# canSlaveV06.net
KiCad netlist of a schematic drawn in EAGLE
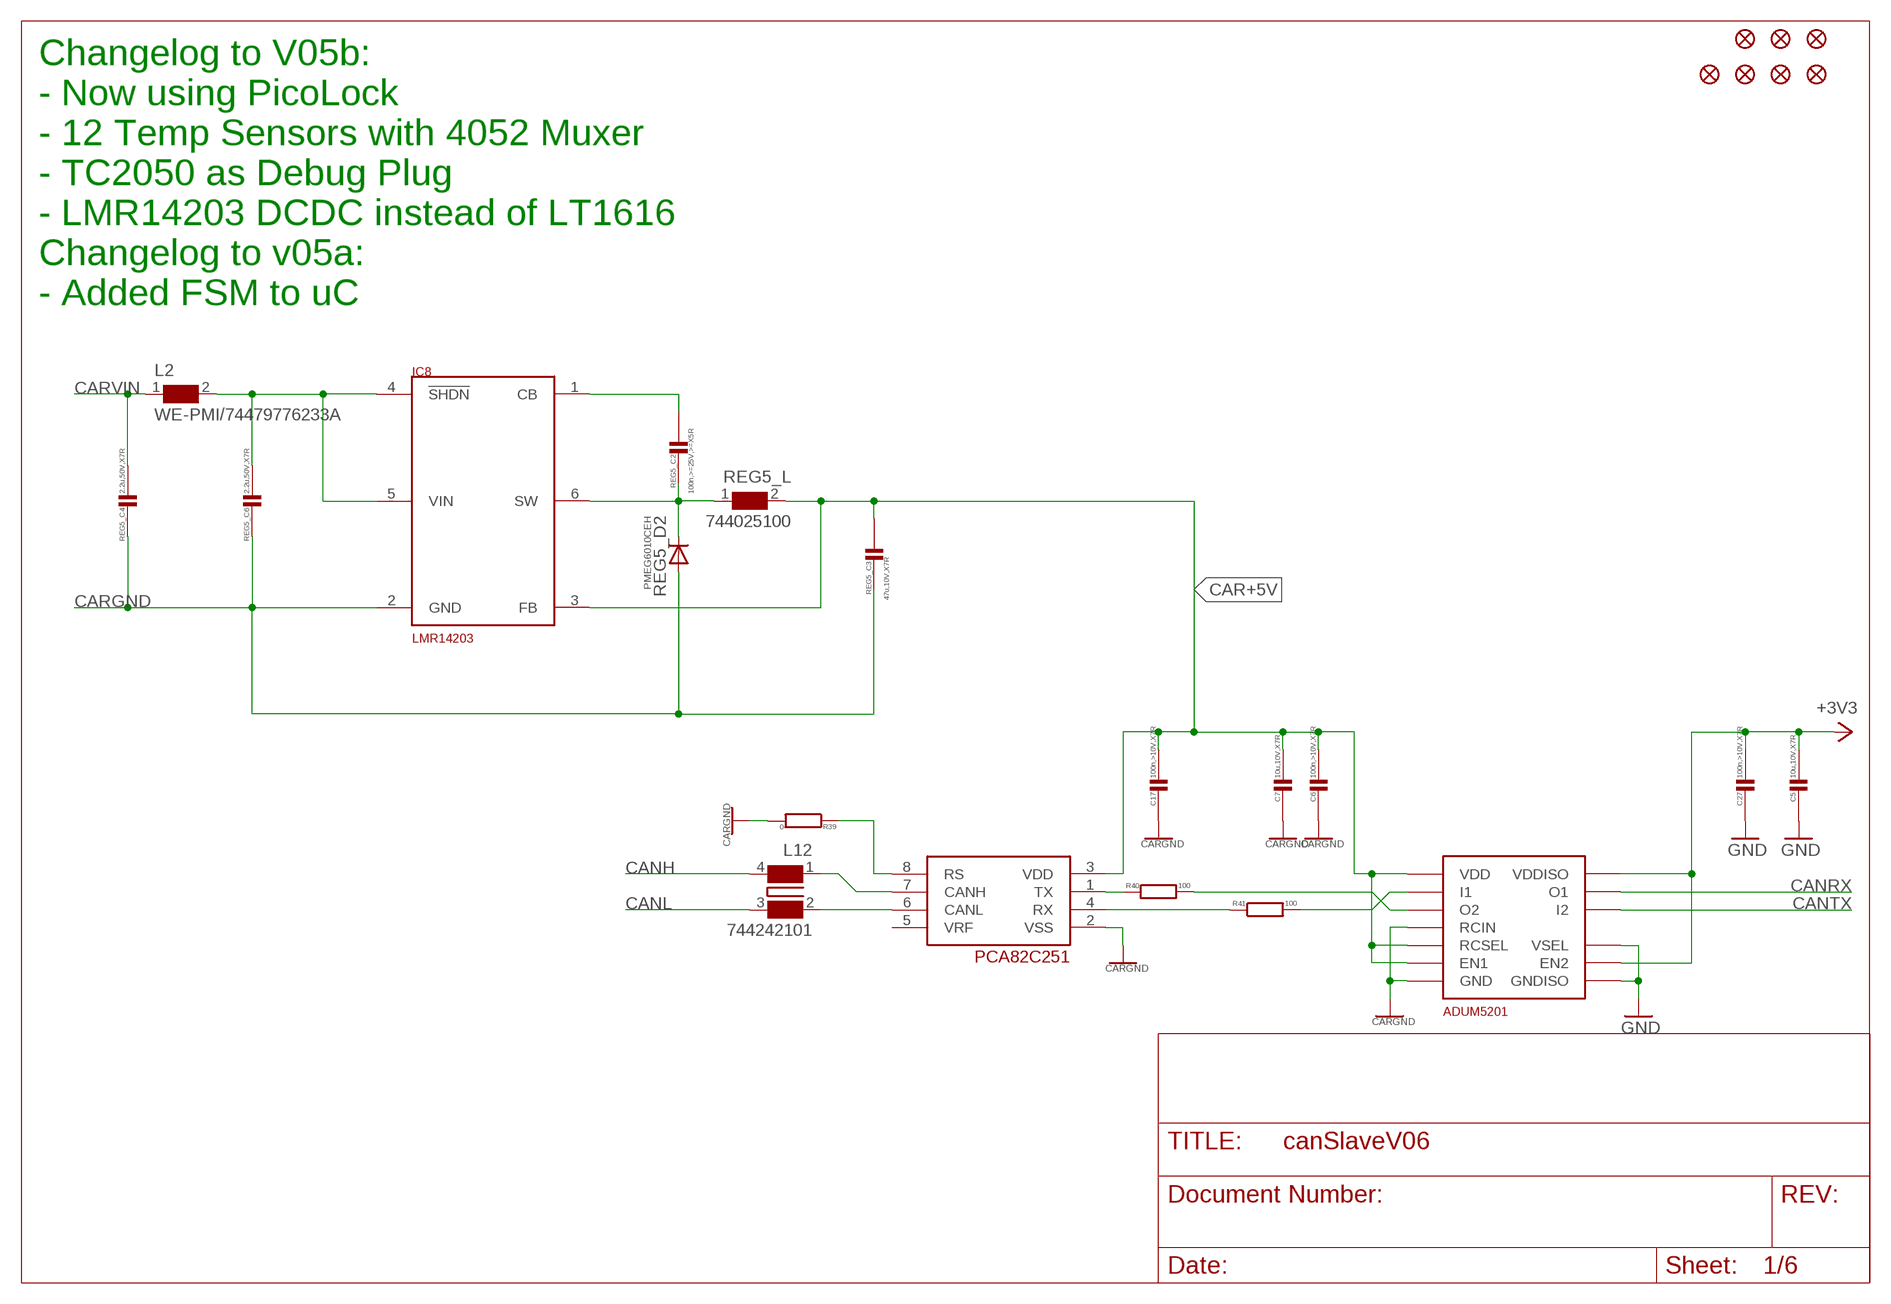
[diagram p0: schematic, sheet 1]
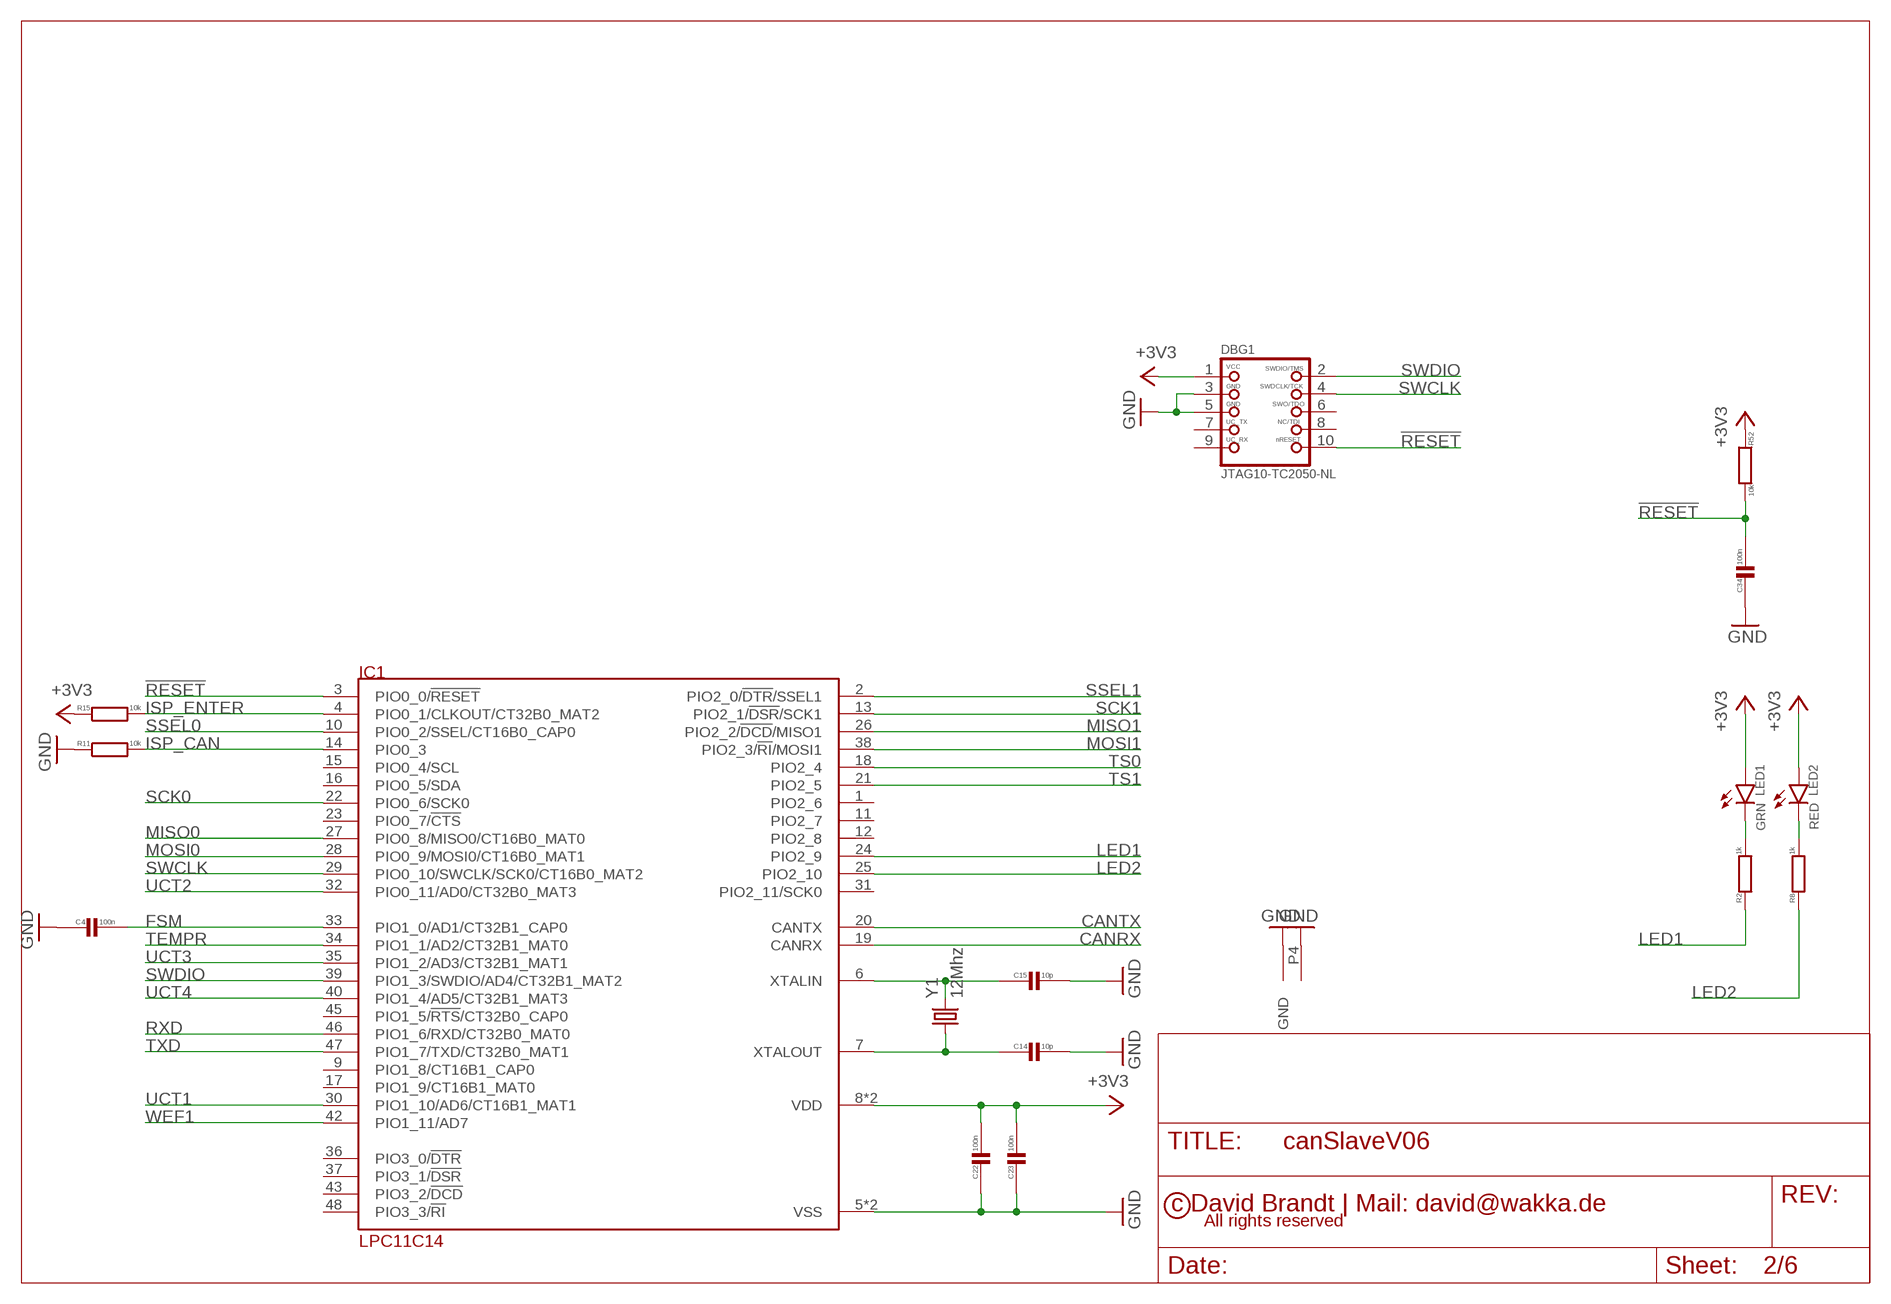
[diagram p1: schematic, sheet 2]
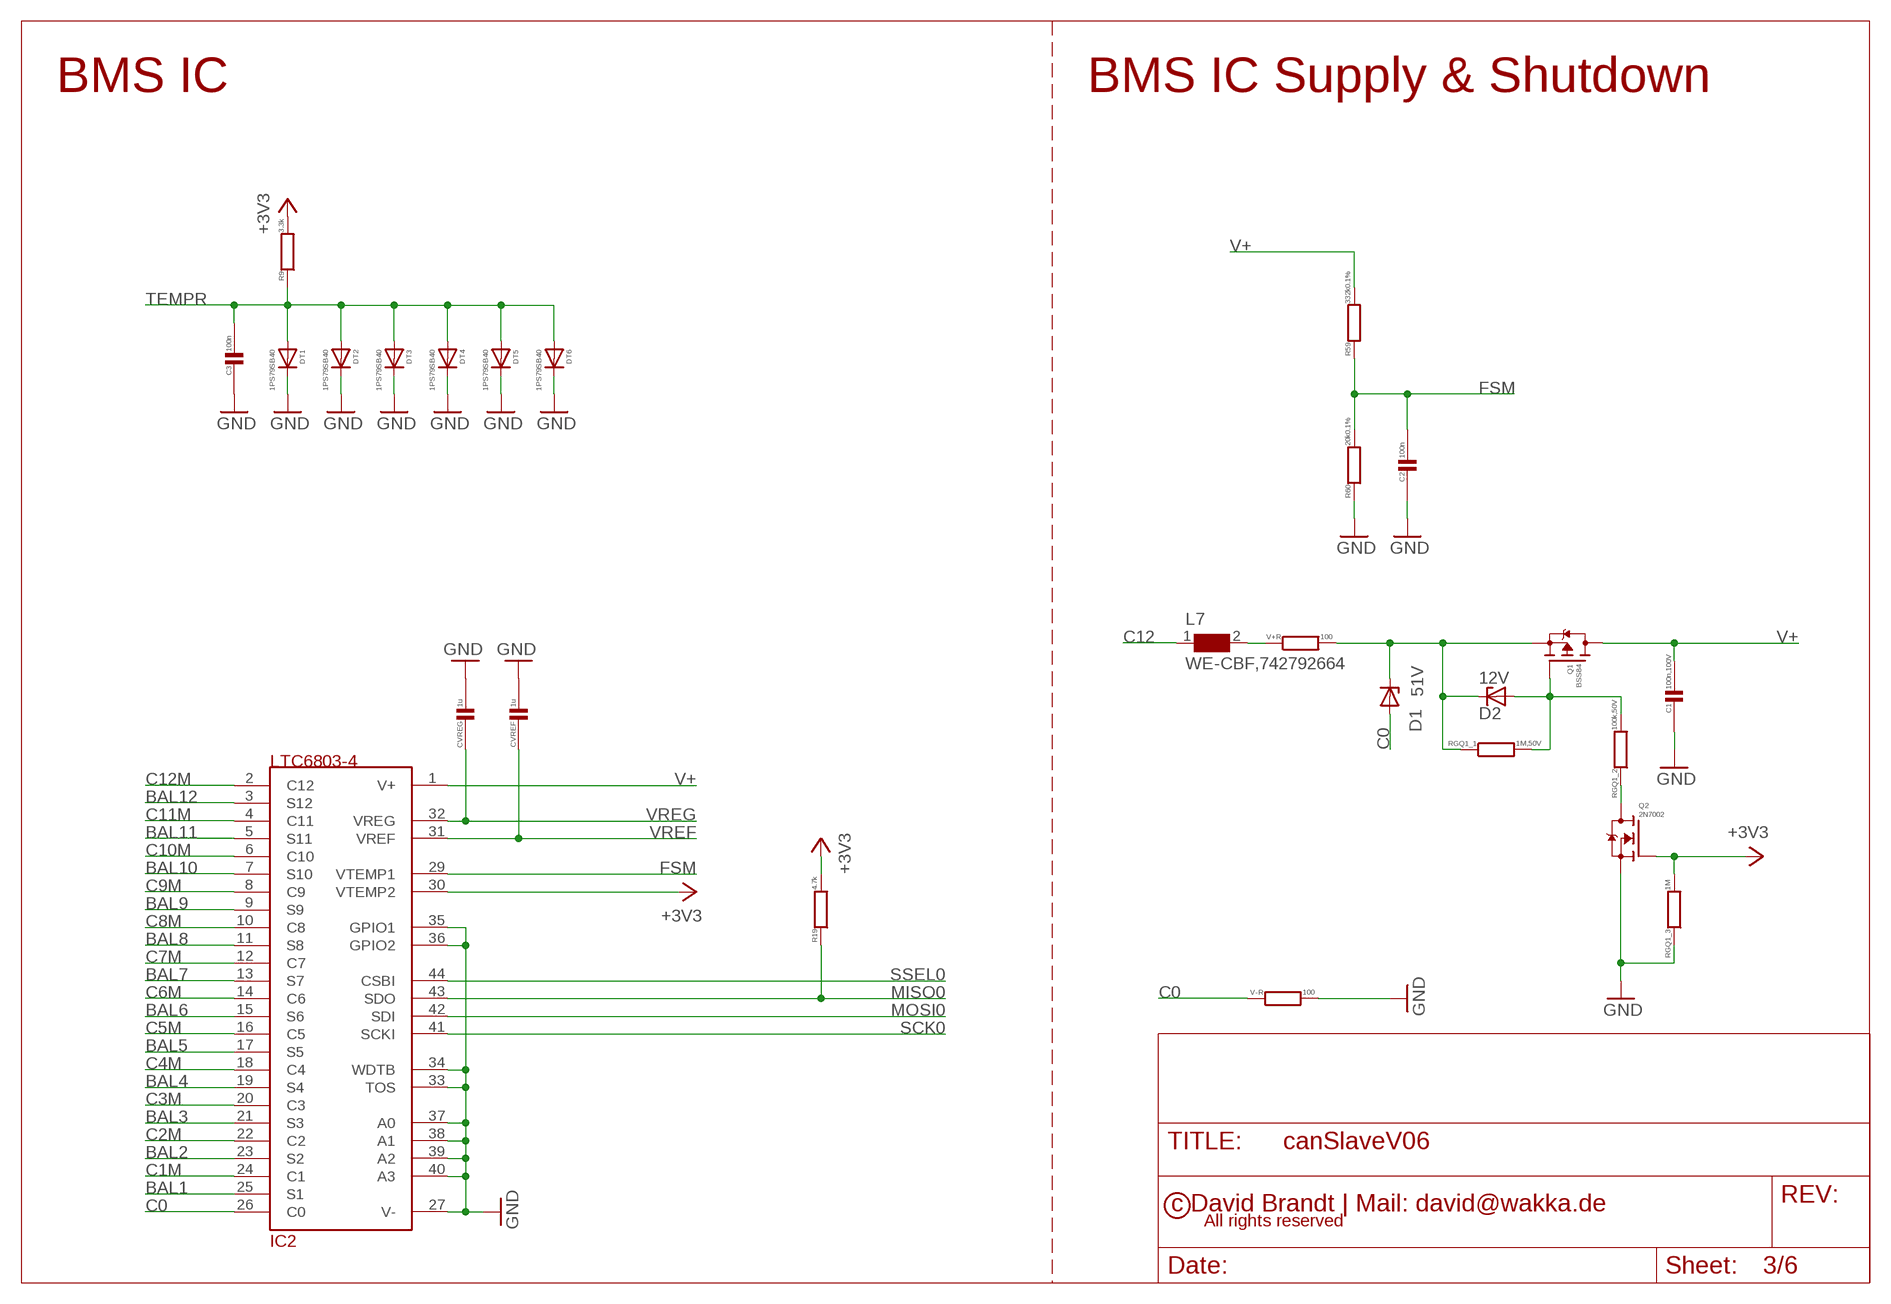
[diagram p2: schematic, sheet 3]
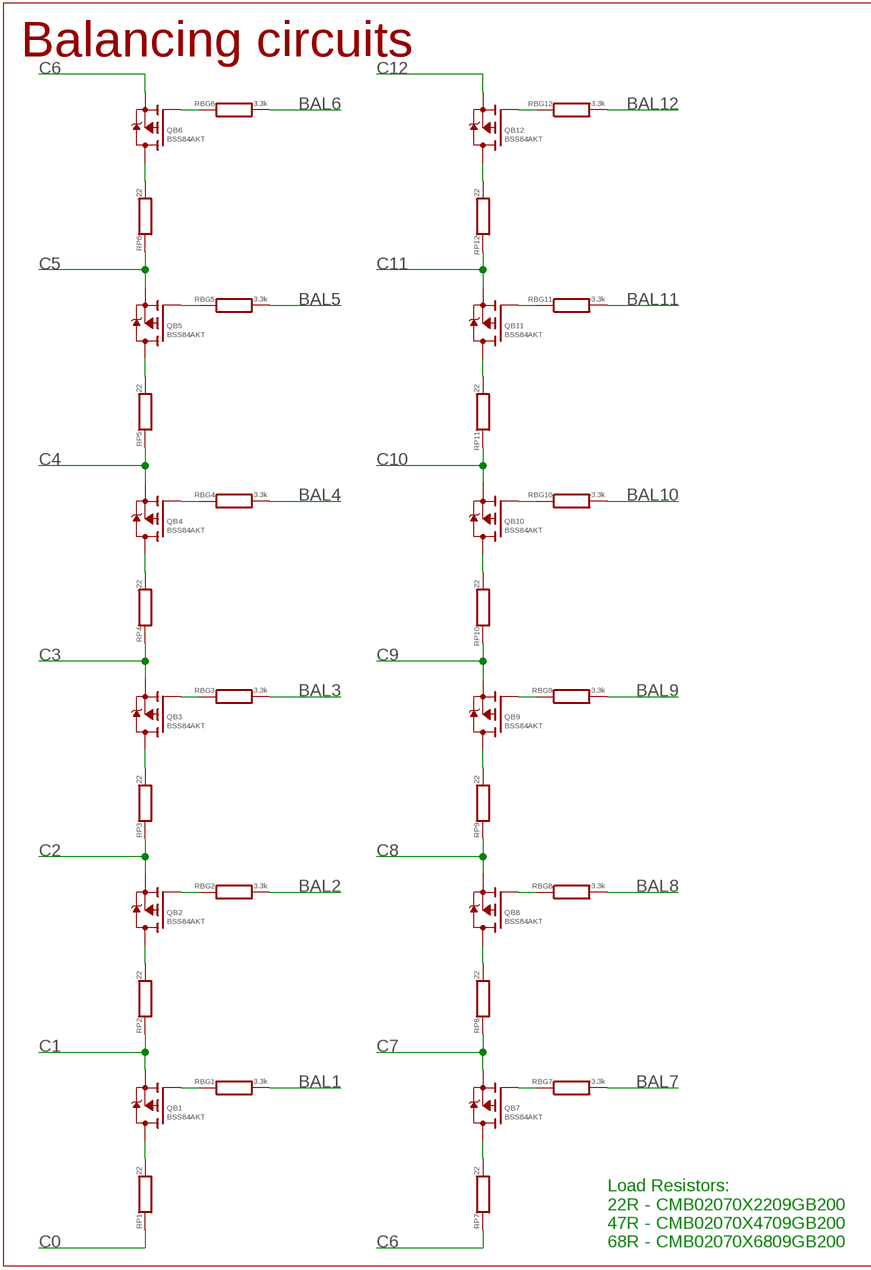
[diagram p3: schematic, sheet 4, part 1 of 2]
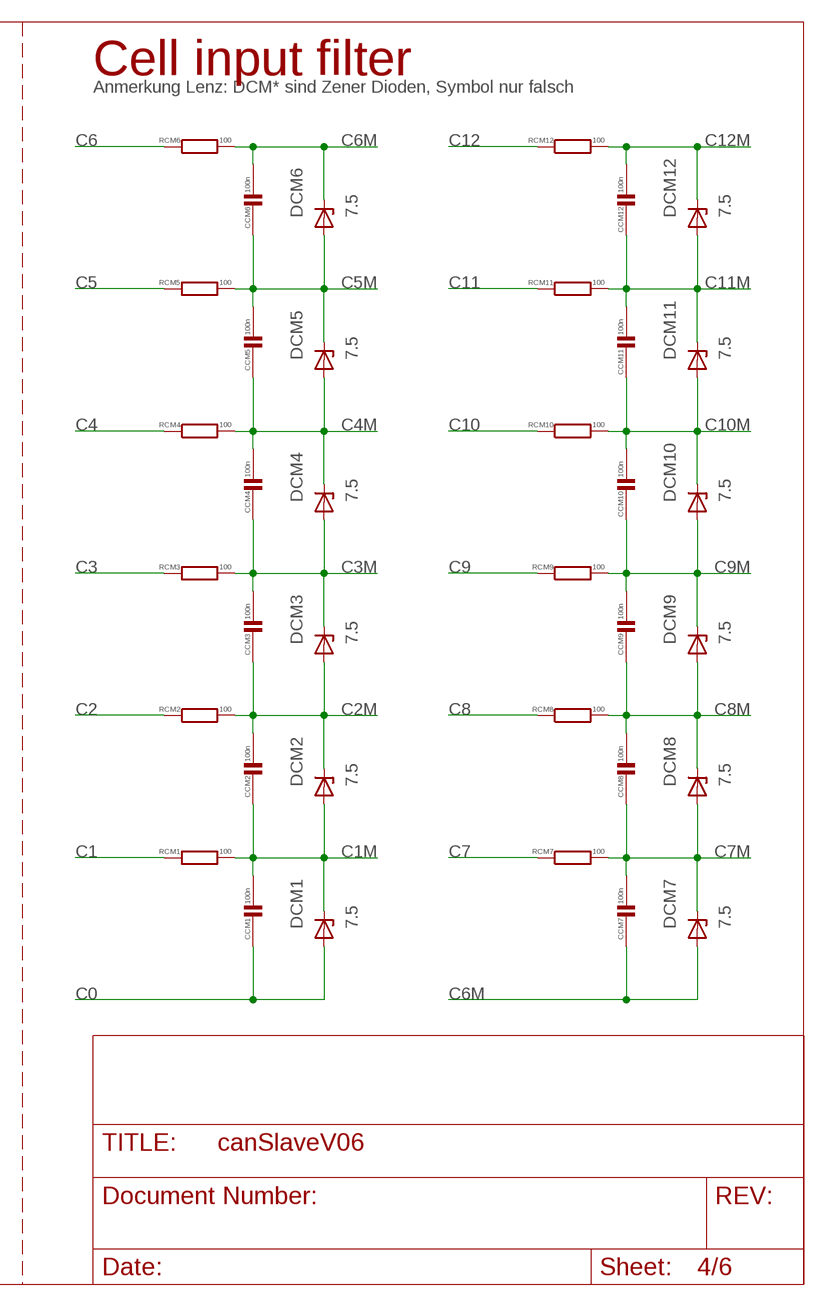
[diagram p4: schematic, sheet 4, part 2 of 2]
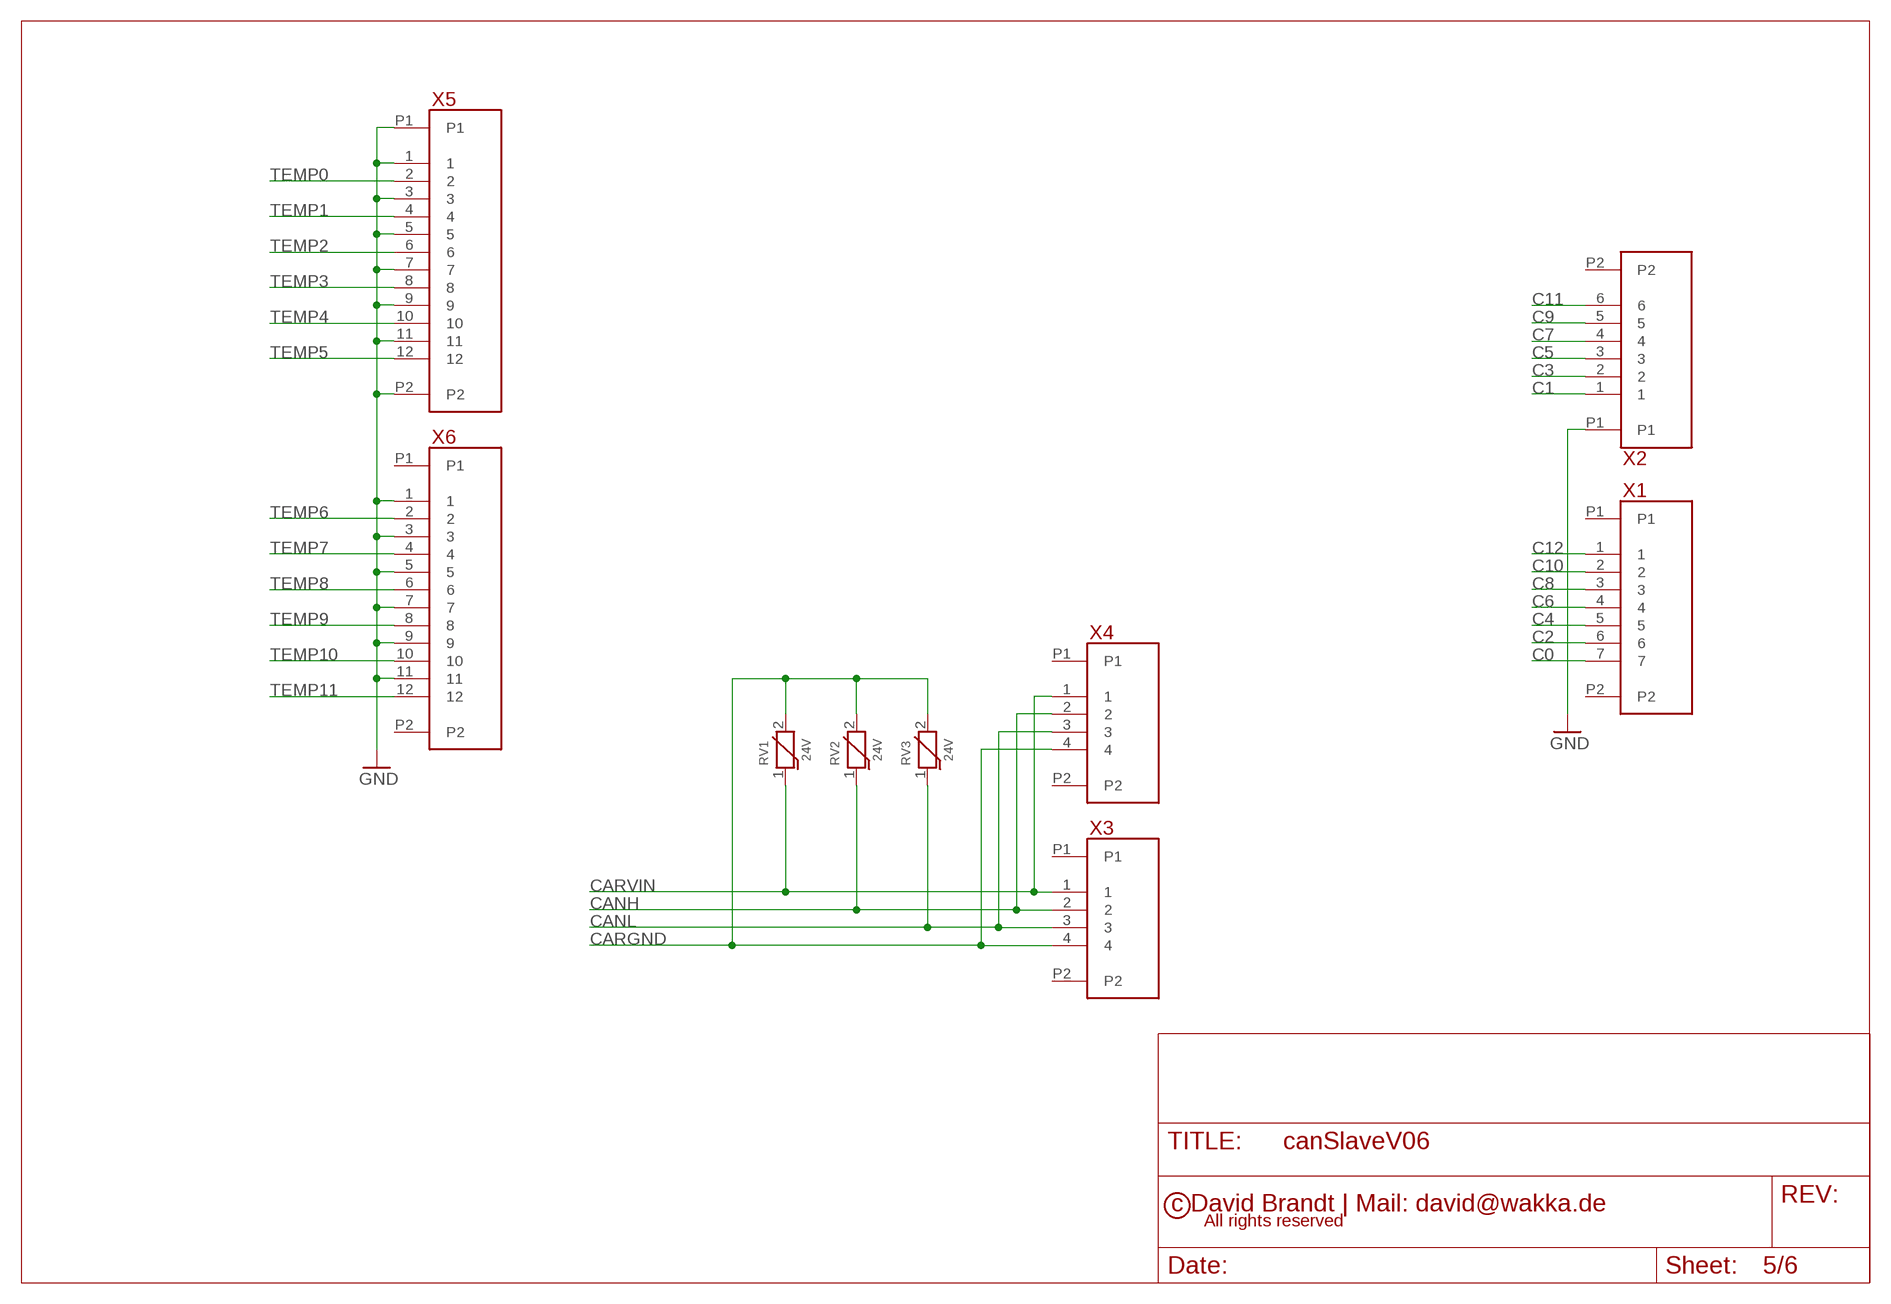
[diagram p5: schematic, sheet 5]
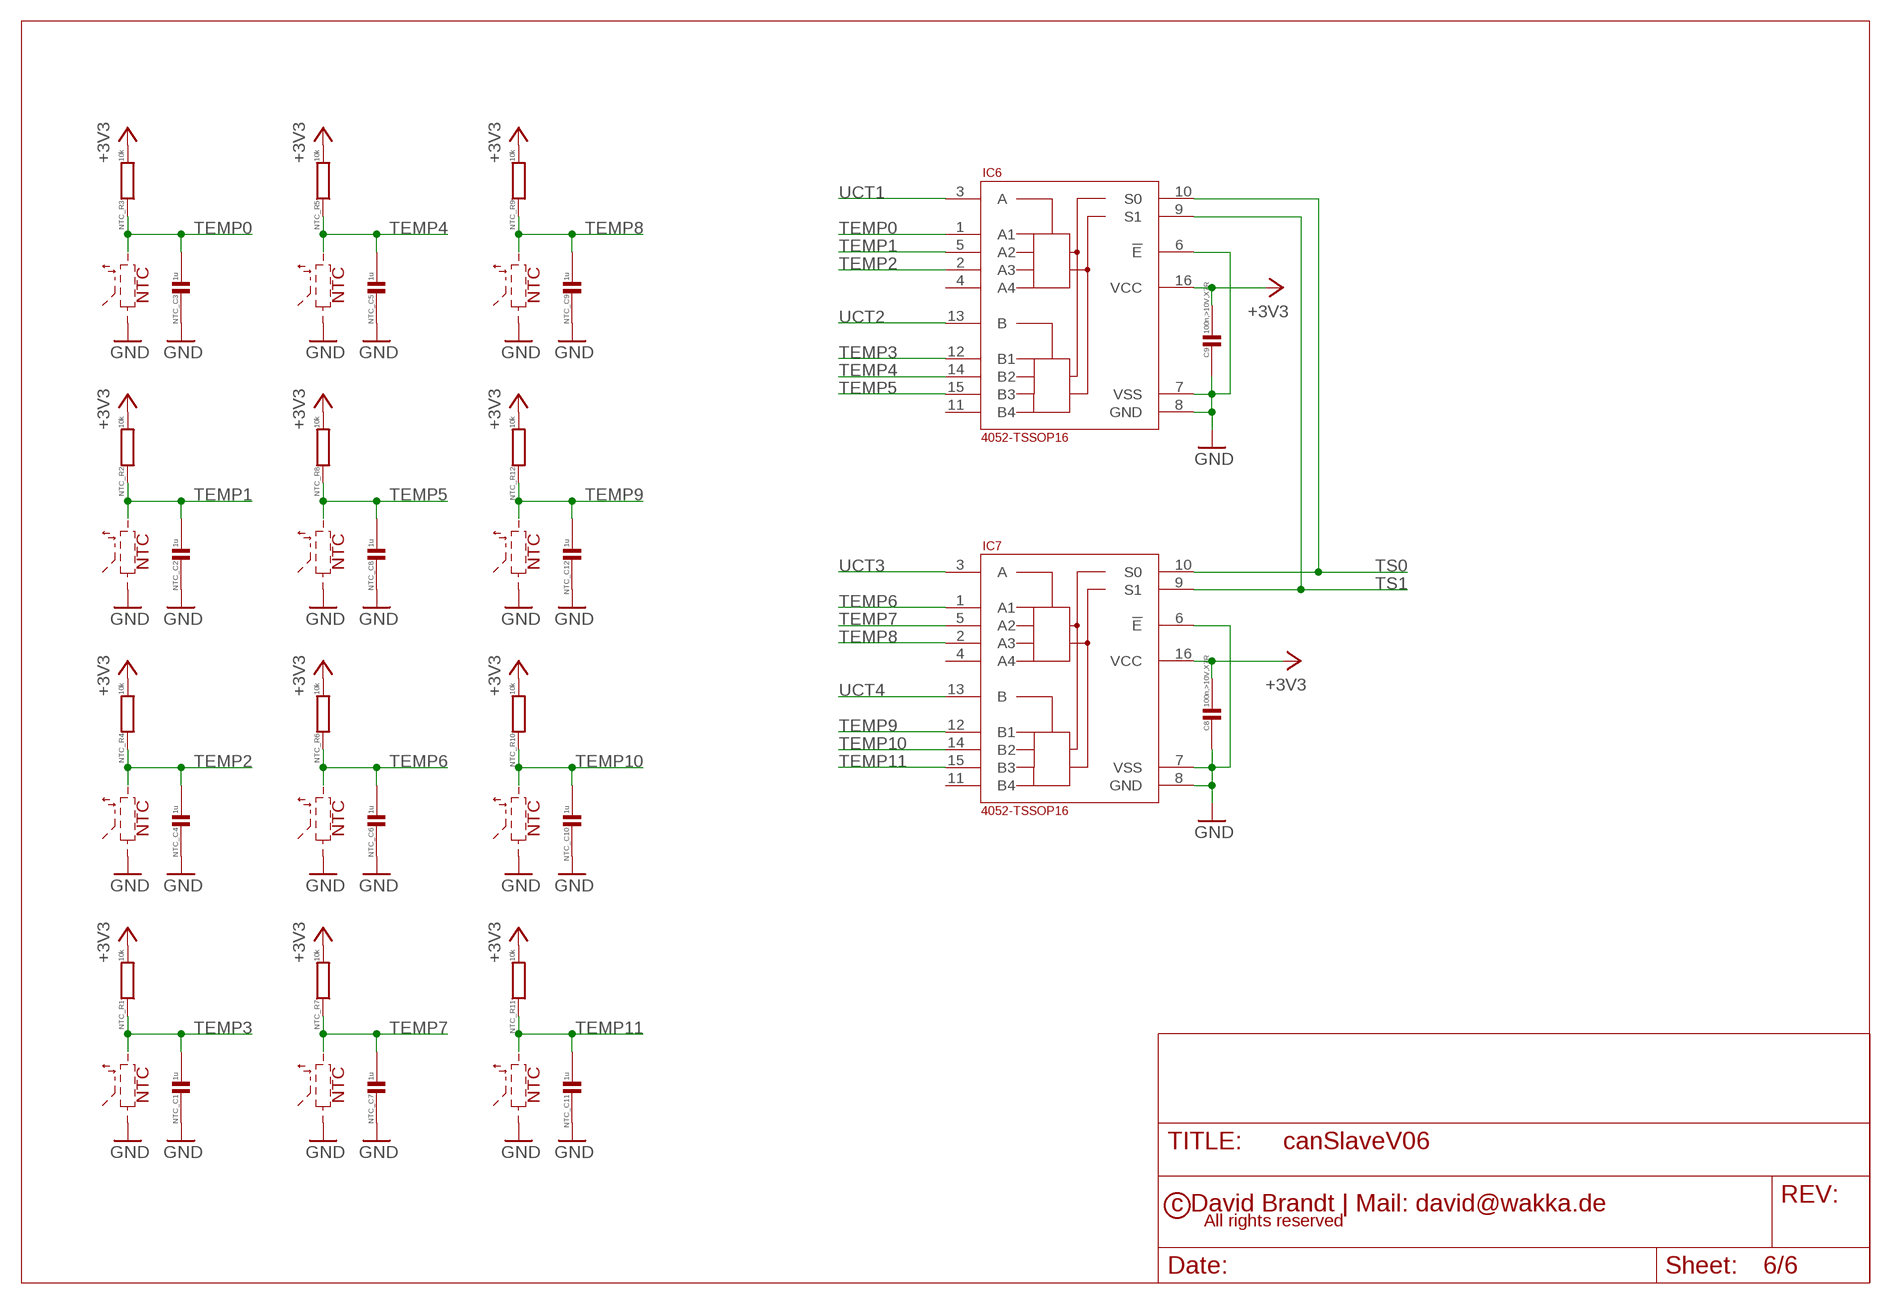
[diagram p6: schematic, sheet 6]

(export (version "E")
  (design (tool "Eeschema 10.0.6"))
  (components
    (comp (ref "C8")
      (value "100n,>10V,X7R")
      (footprint "eagle-import:C0402")
      (libsource (lib "eagle-import") (part "C0402"))
    )
    (comp (ref "C9")
      (value "100n,>10V,X7R")
      (footprint "eagle-import:C0402")
      (libsource (lib "eagle-import") (part "C0402"))
    )
    (comp (ref "IC6")
      (value "4052-TSSOP16")
      (footprint "eagle-import:TSSOP16")
      (libsource (lib "eagle-import") (part "4052-TSSOP16"))
    )
    (comp (ref "IC7")
      (value "4052-TSSOP16")
      (footprint "eagle-import:TSSOP16")
      (libsource (lib "eagle-import") (part "4052-TSSOP16"))
    )
    (comp (ref "NTC_C1")
      (value "1u")
      (footprint "eagle-import:C0402")
      (libsource (lib "eagle-import") (part "C0402"))
    )
    (comp (ref "NTC_C2")
      (value "1u")
      (footprint "eagle-import:C0402")
      (libsource (lib "eagle-import") (part "C0402"))
    )
    (comp (ref "NTC_C3")
      (value "1u")
      (footprint "eagle-import:C0402")
      (libsource (lib "eagle-import") (part "C0402"))
    )
    (comp (ref "NTC_C4")
      (value "1u")
      (footprint "eagle-import:C0402")
      (libsource (lib "eagle-import") (part "C0402"))
    )
    (comp (ref "NTC_C5")
      (value "1u")
      (footprint "eagle-import:C0402")
      (libsource (lib "eagle-import") (part "C0402"))
    )
    (comp (ref "NTC_C6")
      (value "1u")
      (footprint "eagle-import:C0402")
      (libsource (lib "eagle-import") (part "C0402"))
    )
    (comp (ref "NTC_C7")
      (value "1u")
      (footprint "eagle-import:C0402")
      (libsource (lib "eagle-import") (part "C0402"))
    )
    (comp (ref "NTC_C8")
      (value "1u")
      (footprint "eagle-import:C0402")
      (libsource (lib "eagle-import") (part "C0402"))
    )
    (comp (ref "NTC_C9")
      (value "1u")
      (footprint "eagle-import:C0402")
      (libsource (lib "eagle-import") (part "C0402"))
    )
    (comp (ref "NTC_C10")
      (value "1u")
      (footprint "eagle-import:C0402")
      (libsource (lib "eagle-import") (part "C0402"))
    )
    (comp (ref "NTC_C11")
      (value "1u")
      (footprint "eagle-import:C0402")
      (libsource (lib "eagle-import") (part "C0402"))
    )
    (comp (ref "NTC_C12")
      (value "1u")
      (footprint "eagle-import:C0402")
      (libsource (lib "eagle-import") (part "C0402"))
    )
    (comp (ref "NTC_R1")
      (value "10k")
      (footprint "eagle-import:R0402")
      (libsource (lib "eagle-import") (part "R0402"))
    )
    (comp (ref "NTC_R2")
      (value "10k")
      (footprint "eagle-import:R0402")
      (libsource (lib "eagle-import") (part "R0402"))
    )
    (comp (ref "NTC_R3")
      (value "10k")
      (footprint "eagle-import:R0402")
      (libsource (lib "eagle-import") (part "R0402"))
    )
    (comp (ref "NTC_R4")
      (value "10k")
      (footprint "eagle-import:R0402")
      (libsource (lib "eagle-import") (part "R0402"))
    )
    (comp (ref "NTC_R5")
      (value "10k")
      (footprint "eagle-import:R0402")
      (libsource (lib "eagle-import") (part "R0402"))
    )
    (comp (ref "NTC_R6")
      (value "10k")
      (footprint "eagle-import:R0402")
      (libsource (lib "eagle-import") (part "R0402"))
    )
    (comp (ref "NTC_R7")
      (value "10k")
      (footprint "eagle-import:R0402")
      (libsource (lib "eagle-import") (part "R0402"))
    )
    (comp (ref "NTC_R8")
      (value "10k")
      (footprint "eagle-import:R0402")
      (libsource (lib "eagle-import") (part "R0402"))
    )
    (comp (ref "NTC_R9")
      (value "10k")
      (footprint "eagle-import:R0402")
      (libsource (lib "eagle-import") (part "R0402"))
    )
    (comp (ref "NTC_R10")
      (value "10k")
      (footprint "eagle-import:R0402")
      (libsource (lib "eagle-import") (part "R0402"))
    )
    (comp (ref "NTC_R11")
      (value "10k")
      (footprint "eagle-import:R0402")
      (libsource (lib "eagle-import") (part "R0402"))
    )
    (comp (ref "NTC_R12")
      (value "10k")
      (footprint "eagle-import:R0402")
      (libsource (lib "eagle-import") (part "R0402"))
    )
    (comp (ref "CCM1")
      (value "100n")
      (footprint "eagle-import:C0402")
      (libsource (lib "eagle-import") (part "C0402"))
    )
    (comp (ref "CCM2")
      (value "100n")
      (footprint "eagle-import:C0402")
      (libsource (lib "eagle-import") (part "C0402"))
    )
    (comp (ref "CCM3")
      (value "100n")
      (footprint "eagle-import:C0402")
      (libsource (lib "eagle-import") (part "C0402"))
    )
    (comp (ref "CCM4")
      (value "100n")
      (footprint "eagle-import:C0402")
      (libsource (lib "eagle-import") (part "C0402"))
    )
    (comp (ref "CCM5")
      (value "100n")
      (footprint "eagle-import:C0402")
      (libsource (lib "eagle-import") (part "C0402"))
    )
    (comp (ref "CCM6")
      (value "100n")
      (footprint "eagle-import:C0402")
      (libsource (lib "eagle-import") (part "C0402"))
    )
    (comp (ref "CCM7")
      (value "100n")
      (footprint "eagle-import:C0402")
      (libsource (lib "eagle-import") (part "C0402"))
    )
    (comp (ref "CCM8")
      (value "100n")
      (footprint "eagle-import:C0402")
      (libsource (lib "eagle-import") (part "C0402"))
    )
    (comp (ref "CCM9")
      (value "100n")
      (footprint "eagle-import:C0402")
      (libsource (lib "eagle-import") (part "C0402"))
    )
    (comp (ref "CCM10")
      (value "100n")
      (footprint "eagle-import:C0402")
      (libsource (lib "eagle-import") (part "C0402"))
    )
    (comp (ref "CCM11")
      (value "100n")
      (footprint "eagle-import:C0402")
      (libsource (lib "eagle-import") (part "C0402"))
    )
    (comp (ref "CCM12")
      (value "100n")
      (footprint "eagle-import:C0402")
      (libsource (lib "eagle-import") (part "C0402"))
    )
    (comp (ref "DCM1")
      (value "7.5")
      (footprint "eagle-import:SOD523")
      (libsource (lib "eagle-import") (part "ZENERSOD523"))
    )
    (comp (ref "DCM2")
      (value "7.5")
      (footprint "eagle-import:SOD523")
      (libsource (lib "eagle-import") (part "ZENERSOD523"))
    )
    (comp (ref "DCM3")
      (value "7.5")
      (footprint "eagle-import:SOD523")
      (libsource (lib "eagle-import") (part "ZENERSOD523"))
    )
    (comp (ref "DCM4")
      (value "7.5")
      (footprint "eagle-import:SOD523")
      (libsource (lib "eagle-import") (part "ZENERSOD523"))
    )
    (comp (ref "DCM5")
      (value "7.5")
      (footprint "eagle-import:SOD523")
      (libsource (lib "eagle-import") (part "ZENERSOD523"))
    )
    (comp (ref "DCM6")
      (value "7.5")
      (footprint "eagle-import:SOD523")
      (libsource (lib "eagle-import") (part "ZENERSOD523"))
    )
    (comp (ref "DCM7")
      (value "7.5")
      (footprint "eagle-import:SOD523")
      (libsource (lib "eagle-import") (part "ZENERSOD523"))
    )
    (comp (ref "DCM8")
      (value "7.5")
      (footprint "eagle-import:SOD523")
      (libsource (lib "eagle-import") (part "ZENERSOD523"))
    )
    (comp (ref "DCM9")
      (value "7.5")
      (footprint "eagle-import:SOD523")
      (libsource (lib "eagle-import") (part "ZENERSOD523"))
    )
    (comp (ref "DCM10")
      (value "7.5")
      (footprint "eagle-import:SOD523")
      (libsource (lib "eagle-import") (part "ZENERSOD523"))
    )
    (comp (ref "DCM11")
      (value "7.5")
      (footprint "eagle-import:SOD523")
      (libsource (lib "eagle-import") (part "ZENERSOD523"))
    )
    (comp (ref "DCM12")
      (value "7.5")
      (footprint "eagle-import:SOD523")
      (libsource (lib "eagle-import") (part "ZENERSOD523"))
    )
    (comp (ref "QB1")
      (value "BSS84AKT")
      (footprint "eagle-import:SOT416")
      (libsource (lib "eagle-import") (part "BSS84AKT"))
    )
    (comp (ref "QB2")
      (value "BSS84AKT")
      (footprint "eagle-import:SOT416")
      (libsource (lib "eagle-import") (part "BSS84AKT"))
    )
    (comp (ref "QB3")
      (value "BSS84AKT")
      (footprint "eagle-import:SOT416")
      (libsource (lib "eagle-import") (part "BSS84AKT"))
    )
    (comp (ref "QB4")
      (value "BSS84AKT")
      (footprint "eagle-import:SOT416")
      (libsource (lib "eagle-import") (part "BSS84AKT"))
    )
    (comp (ref "QB5")
      (value "BSS84AKT")
      (footprint "eagle-import:SOT416")
      (libsource (lib "eagle-import") (part "BSS84AKT"))
    )
    (comp (ref "QB6")
      (value "BSS84AKT")
      (footprint "eagle-import:SOT416")
      (libsource (lib "eagle-import") (part "BSS84AKT"))
    )
    (comp (ref "QB7")
      (value "BSS84AKT")
      (footprint "eagle-import:SOT416")
      (libsource (lib "eagle-import") (part "BSS84AKT"))
    )
    (comp (ref "QB8")
      (value "BSS84AKT")
      (footprint "eagle-import:SOT416")
      (libsource (lib "eagle-import") (part "BSS84AKT"))
    )
    (comp (ref "QB9")
      (value "BSS84AKT")
      (footprint "eagle-import:SOT416")
      (libsource (lib "eagle-import") (part "BSS84AKT"))
    )
    (comp (ref "QB10")
      (value "BSS84AKT")
      (footprint "eagle-import:SOT416")
      (libsource (lib "eagle-import") (part "BSS84AKT"))
    )
    (comp (ref "QB11")
      (value "BSS84AKT")
      (footprint "eagle-import:SOT416")
      (libsource (lib "eagle-import") (part "BSS84AKT"))
    )
    (comp (ref "QB12")
      (value "BSS84AKT")
      (footprint "eagle-import:SOT416")
      (libsource (lib "eagle-import") (part "BSS84AKT"))
    )
    (comp (ref "RBG1")
      (value "3.3k")
      (footprint "eagle-import:R0402")
      (libsource (lib "eagle-import") (part "R0402"))
    )
    (comp (ref "RBG2")
      (value "3.3k")
      (footprint "eagle-import:R0402")
      (libsource (lib "eagle-import") (part "R0402"))
    )
    (comp (ref "RBG3")
      (value "3.3k")
      (footprint "eagle-import:R0402")
      (libsource (lib "eagle-import") (part "R0402"))
    )
    (comp (ref "RBG4")
      (value "3.3k")
      (footprint "eagle-import:R0402")
      (libsource (lib "eagle-import") (part "R0402"))
    )
    (comp (ref "RBG5")
      (value "3.3k")
      (footprint "eagle-import:R0402")
      (libsource (lib "eagle-import") (part "R0402"))
    )
    (comp (ref "RBG6")
      (value "3.3k")
      (footprint "eagle-import:R0402")
      (libsource (lib "eagle-import") (part "R0402"))
    )
    (comp (ref "RBG7")
      (value "3.3k")
      (footprint "eagle-import:R0402")
      (libsource (lib "eagle-import") (part "R0402"))
    )
    (comp (ref "RBG8")
      (value "3.3k")
      (footprint "eagle-import:R0402")
      (libsource (lib "eagle-import") (part "R0402"))
    )
    (comp (ref "RBG9")
      (value "3.3k")
      (footprint "eagle-import:R0402")
      (libsource (lib "eagle-import") (part "R0402"))
    )
    (comp (ref "RBG10")
      (value "3.3k")
      (footprint "eagle-import:R0402")
      (libsource (lib "eagle-import") (part "R0402"))
    )
    (comp (ref "RBG11")
      (value "3.3k")
      (footprint "eagle-import:R0402")
      (libsource (lib "eagle-import") (part "R0402"))
    )
    (comp (ref "RBG12")
      (value "3.3k")
      (footprint "eagle-import:R0402")
      (libsource (lib "eagle-import") (part "R0402"))
    )
    (comp (ref "RCM1")
      (value "100")
      (footprint "eagle-import:R0402")
      (libsource (lib "eagle-import") (part "R0402"))
    )
    (comp (ref "RCM2")
      (value "100")
      (footprint "eagle-import:R0402")
      (libsource (lib "eagle-import") (part "R0402"))
    )
    (comp (ref "RCM3")
      (value "100")
      (footprint "eagle-import:R0402")
      (libsource (lib "eagle-import") (part "R0402"))
    )
    (comp (ref "RCM4")
      (value "100")
      (footprint "eagle-import:R0402")
      (libsource (lib "eagle-import") (part "R0402"))
    )
    (comp (ref "RCM5")
      (value "100")
      (footprint "eagle-import:R0402")
      (libsource (lib "eagle-import") (part "R0402"))
    )
    (comp (ref "RCM6")
      (value "100")
      (footprint "eagle-import:R0402")
      (libsource (lib "eagle-import") (part "R0402"))
    )
    (comp (ref "RCM7")
      (value "100")
      (footprint "eagle-import:R0402")
      (libsource (lib "eagle-import") (part "R0402"))
    )
    (comp (ref "RCM8")
      (value "100")
      (footprint "eagle-import:R0402")
      (libsource (lib "eagle-import") (part "R0402"))
    )
    (comp (ref "RCM9")
      (value "100")
      (footprint "eagle-import:R0402")
      (libsource (lib "eagle-import") (part "R0402"))
    )
    (comp (ref "RCM10")
      (value "100")
      (footprint "eagle-import:R0402")
      (libsource (lib "eagle-import") (part "R0402"))
    )
    (comp (ref "RCM11")
      (value "100")
      (footprint "eagle-import:R0402")
      (libsource (lib "eagle-import") (part "R0402"))
    )
    (comp (ref "RCM12")
      (value "100")
      (footprint "eagle-import:R0402")
      (libsource (lib "eagle-import") (part "R0402"))
    )
    (comp (ref "RP1")
      (value "22")
      (footprint "eagle-import:MINI_MELF-0207R")
      (libsource (lib "eagle-import") (part "RMELF-0207R"))
    )
    (comp (ref "RP2")
      (value "22")
      (footprint "eagle-import:MINI_MELF-0207R")
      (libsource (lib "eagle-import") (part "RMELF-0207R"))
    )
    (comp (ref "RP3")
      (value "22")
      (footprint "eagle-import:MINI_MELF-0207R")
      (libsource (lib "eagle-import") (part "RMELF-0207R"))
    )
    (comp (ref "RP4")
      (value "22")
      (footprint "eagle-import:MINI_MELF-0207R")
      (libsource (lib "eagle-import") (part "RMELF-0207R"))
    )
    (comp (ref "RP5")
      (value "22")
      (footprint "eagle-import:MINI_MELF-0207R")
      (libsource (lib "eagle-import") (part "RMELF-0207R"))
    )
    (comp (ref "RP6")
      (value "22")
      (footprint "eagle-import:MINI_MELF-0207R")
      (libsource (lib "eagle-import") (part "RMELF-0207R"))
    )
    (comp (ref "RP7")
      (value "22")
      (footprint "eagle-import:MINI_MELF-0207R")
      (libsource (lib "eagle-import") (part "RMELF-0207R"))
    )
    (comp (ref "RP8")
      (value "22")
      (footprint "eagle-import:MINI_MELF-0207R")
      (libsource (lib "eagle-import") (part "RMELF-0207R"))
    )
    (comp (ref "RP9")
      (value "22")
      (footprint "eagle-import:MINI_MELF-0207R")
      (libsource (lib "eagle-import") (part "RMELF-0207R"))
    )
    (comp (ref "RP10")
      (value "22")
      (footprint "eagle-import:MINI_MELF-0207R")
      (libsource (lib "eagle-import") (part "RMELF-0207R"))
    )
    (comp (ref "RP11")
      (value "22")
      (footprint "eagle-import:MINI_MELF-0207R")
      (libsource (lib "eagle-import") (part "RMELF-0207R"))
    )
    (comp (ref "RP12")
      (value "22")
      (footprint "eagle-import:MINI_MELF-0207R")
      (libsource (lib "eagle-import") (part "RMELF-0207R"))
    )
    (comp (ref "C1")
      (value "100n,100V")
      (footprint "eagle-import:C0603")
      (libsource (lib "eagle-import") (part "C0603"))
    )
    (comp (ref "C2")
      (value "100n")
      (footprint "eagle-import:C0402")
      (libsource (lib "eagle-import") (part "C0402"))
    )
    (comp (ref "C3")
      (value "100n")
      (footprint "eagle-import:C0402")
      (libsource (lib "eagle-import") (part "C0402"))
    )
    (comp (ref "CVREF")
      (value "1u")
      (footprint "eagle-import:C0402")
      (libsource (lib "eagle-import") (part "C0402"))
    )
    (comp (ref "CVREG")
      (value "1u")
      (footprint "eagle-import:C0402")
      (libsource (lib "eagle-import") (part "C0402"))
    )
    (comp (ref "D1")
      (value "51V")
      (footprint "eagle-import:SOD323-L")
      (libsource (lib "eagle-import") (part "ZENERSOD323"))
    )
    (comp (ref "D2")
      (value "12V")
      (footprint "eagle-import:SOD323-L")
      (libsource (lib "eagle-import") (part "ZENERSOD323"))
    )
    (comp (ref "DT1")
      (value "1PS79SB40")
      (footprint "eagle-import:SOD523")
      (libsource (lib "eagle-import") (part "DIODE-SOD523"))
    )
    (comp (ref "DT2")
      (value "1PS79SB40")
      (footprint "eagle-import:SOD523")
      (libsource (lib "eagle-import") (part "DIODE-SOD523"))
    )
    (comp (ref "DT3")
      (value "1PS79SB40")
      (footprint "eagle-import:SOD523")
      (libsource (lib "eagle-import") (part "DIODE-SOD523"))
    )
    (comp (ref "DT4")
      (value "1PS79SB40")
      (footprint "eagle-import:SOD523")
      (libsource (lib "eagle-import") (part "DIODE-SOD523"))
    )
    (comp (ref "DT5")
      (value "1PS79SB40")
      (footprint "eagle-import:SOD523")
      (libsource (lib "eagle-import") (part "DIODE-SOD523"))
    )
    (comp (ref "DT6")
      (value "1PS79SB40")
      (footprint "eagle-import:SOD523")
      (libsource (lib "eagle-import") (part "DIODE-SOD523"))
    )
    (comp (ref "IC2")
      (value "LTC6803-4")
      (footprint "eagle-import:44SSOP")
      (libsource (lib "eagle-import") (part "LTC6803-4"))
    )
    (comp (ref "L7")
      (value "WE-CBF,742792664")
      (footprint "eagle-import:0603")
      (libsource (lib "eagle-import") (part "WE-CBF_0603"))
    )
    (comp (ref "Q1")
      (value "BSS84")
      (footprint "eagle-import:SOT23")
      (libsource (lib "eagle-import") (part "BSS84"))
    )
    (comp (ref "Q2")
      (value "2N7002")
      (footprint "eagle-import:SOT23")
      (libsource (lib "eagle-import") (part "2N7002"))
    )
    (comp (ref "R9")
      (value "3.3k")
      (footprint "eagle-import:R0603")
      (libsource (lib "eagle-import") (part "R0603"))
    )
    (comp (ref "R19")
      (value "4.7k")
      (footprint "eagle-import:R0402")
      (libsource (lib "eagle-import") (part "R0402"))
    )
    (comp (ref "R59")
      (value "332k0.1%")
      (footprint "eagle-import:R0603")
      (libsource (lib "eagle-import") (part "R0603"))
    )
    (comp (ref "R60")
      (value "20k0.1%")
      (footprint "eagle-import:R0402")
      (libsource (lib "eagle-import") (part "R0402"))
    )
    (comp (ref "RGQ1_1")
      (value "1M,50V")
      (footprint "eagle-import:R0603")
      (libsource (lib "eagle-import") (part "R0603"))
    )
    (comp (ref "RGQ1_2")
      (value "100k,50V")
      (footprint "eagle-import:R0603")
      (libsource (lib "eagle-import") (part "R0603"))
    )
    (comp (ref "RGQ1_3")
      (value "1M")
      (footprint "eagle-import:R0402")
      (libsource (lib "eagle-import") (part "R0402"))
    )
    (comp (ref "V+R")
      (value "100")
      (footprint "eagle-import:R0603")
      (libsource (lib "eagle-import") (part "R0603"))
    )
    (comp (ref "V-R")
      (value "100")
      (footprint "eagle-import:R0603")
      (libsource (lib "eagle-import") (part "R0603"))
    )
    (comp (ref "C5")
      (value "10u,10V,X7R")
      (footprint "eagle-import:C0603")
      (libsource (lib "eagle-import") (part "C0603"))
    )
    (comp (ref "C6")
      (value "100n,>10V,X7R")
      (footprint "eagle-import:C0402")
      (libsource (lib "eagle-import") (part "C0402"))
    )
    (comp (ref "C7")
      (value "10u,10V,X7R")
      (footprint "eagle-import:C0603")
      (libsource (lib "eagle-import") (part "C0603"))
    )
    (comp (ref "C17")
      (value "100n,>10V,X7R")
      (footprint "eagle-import:C0402")
      (libsource (lib "eagle-import") (part "C0402"))
    )
    (comp (ref "C27")
      (value "100n,>10V,X7R")
      (footprint "eagle-import:C0402")
      (libsource (lib "eagle-import") (part "C0402"))
    )
    (comp (ref "FID2")
      (value "FIDUCIAL\"\"")
      (footprint "eagle-import:FIDUCIAL_1MM")
      (libsource (lib "eagle-import") (part "FIDUCIAL{dblquote}{dblquote}"))
    )
    (comp (ref "FID3")
      (value "FIDUCIAL\"\"")
      (footprint "eagle-import:FIDUCIAL_1MM")
      (libsource (lib "eagle-import") (part "FIDUCIAL{dblquote}{dblquote}"))
    )
    (comp (ref "FID4")
      (value "FIDUCIAL\"\"")
      (footprint "eagle-import:FIDUCIAL_1MM")
      (libsource (lib "eagle-import") (part "FIDUCIAL{dblquote}{dblquote}"))
    )
    (comp (ref "FID7")
      (value "FIDUCIAL\"\"")
      (footprint "eagle-import:FIDUCIAL_1MM")
      (libsource (lib "eagle-import") (part "FIDUCIAL{dblquote}{dblquote}"))
    )
    (comp (ref "FID8")
      (value "FIDUCIAL\"\"")
      (footprint "eagle-import:FIDUCIAL_1MM")
      (libsource (lib "eagle-import") (part "FIDUCIAL{dblquote}{dblquote}"))
    )
    (comp (ref "FID9")
      (value "FIDUCIAL\"\"")
      (footprint "eagle-import:FIDUCIAL_1MM")
      (libsource (lib "eagle-import") (part "FIDUCIAL{dblquote}{dblquote}"))
    )
    (comp (ref "FID10")
      (value "FIDUCIAL\"\"")
      (footprint "eagle-import:FIDUCIAL_1MM")
      (libsource (lib "eagle-import") (part "FIDUCIAL{dblquote}{dblquote}"))
    )
    (comp (ref "IC4")
      (value "PCA82C251")
      (footprint "eagle-import:SO-8")
      (libsource (lib "eagle-import") (part "MCP2551"))
    )
    (comp (ref "IC5")
      (value "ADUM5201")
      (footprint "eagle-import:SO16WB")
      (libsource (lib "eagle-import") (part "ADUM5201"))
    )
    (comp (ref "IC8")
      (value "LMR14203")
      (footprint "eagle-import:SOT23-6")
      (libsource (lib "eagle-import") (part "LMR1420X"))
    )
    (comp (ref "L2")
      (value "WE-PMI/74479776233A")
      (footprint "eagle-import:WE-PMI_0806")
      (libsource (lib "eagle-import") (part "WE-PMI_0806"))
    )
    (comp (ref "L12")
      (value "744242101")
      (footprint "eagle-import:WE-SLM")
      (libsource (lib "eagle-import") (part "WE-SLM"))
    )
    (comp (ref "R39")
      (value "0")
      (footprint "eagle-import:R0402")
      (libsource (lib "eagle-import") (part "R0402"))
    )
    (comp (ref "R40")
      (value "100")
      (footprint "eagle-import:R0402")
      (libsource (lib "eagle-import") (part "R0402"))
    )
    (comp (ref "R41")
      (value "100")
      (footprint "eagle-import:R0402")
      (libsource (lib "eagle-import") (part "R0402"))
    )
    (comp (ref "REG5_C2")
      (value "100n,>=25V,>=X5R")
      (footprint "eagle-import:C0402")
      (libsource (lib "eagle-import") (part "C0402"))
    )
    (comp (ref "REG5_C3")
      (value "47u,10V,X7R")
      (footprint "eagle-import:C1210")
      (libsource (lib "eagle-import") (part "C1210"))
    )
    (comp (ref "REG5_C4")
      (value "2.2u,50V,X7R")
      (footprint "eagle-import:C0805")
      (libsource (lib "eagle-import") (part "C0805"))
    )
    (comp (ref "REG5_C6")
      (value "2.2u,50V,X7R")
      (footprint "eagle-import:C0805")
      (libsource (lib "eagle-import") (part "C0805"))
    )
    (comp (ref "REG5_D2")
      (value "PMEG6010CEH")
      (footprint "eagle-import:SOD123")
      (libsource (lib "eagle-import") (part "D-SOD123"))
    )
    (comp (ref "REG5_L")
      (value "744025100")
      (footprint "eagle-import:WE-TPC_2828")
      (libsource (lib "eagle-import") (part "WE-TPC_2828"))
    )
    (comp (ref "C4")
      (value "100n")
      (footprint "eagle-import:C0402")
      (libsource (lib "eagle-import") (part "C0402"))
    )
    (comp (ref "C14")
      (value "10p")
      (footprint "eagle-import:C0402")
      (libsource (lib "eagle-import") (part "C0402"))
    )
    (comp (ref "C15")
      (value "10p")
      (footprint "eagle-import:C0402")
      (libsource (lib "eagle-import") (part "C0402"))
    )
    (comp (ref "C22")
      (value "100n")
      (footprint "eagle-import:C0402")
      (libsource (lib "eagle-import") (part "C0402"))
    )
    (comp (ref "C23")
      (value "100n")
      (footprint "eagle-import:C0402")
      (libsource (lib "eagle-import") (part "C0402"))
    )
    (comp (ref "C34")
      (value "100n")
      (footprint "eagle-import:C0402")
      (libsource (lib "eagle-import") (part "C0402"))
    )
    (comp (ref "DBG1")
      (value "JTAG10-TC2050-NL")
      (footprint "eagle-import:TC2050-NL-JTORDER")
      (libsource (lib "eagle-import") (part "JTAG10-TC2050-NL"))
    )
    (comp (ref "IC1")
      (value "LPC11C14")
      (footprint "eagle-import:LQFP48")
      (libsource (lib "eagle-import") (part "LPC11C1X"))
    )
    (comp (ref "LED1")
      (value "GRN")
      (footprint "eagle-import:CHIPLED_0603")
      (libsource (lib "eagle-import") (part "LED0603"))
    )
    (comp (ref "LED2")
      (value "RED")
      (footprint "eagle-import:CHIPLED_0603")
      (libsource (lib "eagle-import") (part "LED0603"))
    )
    (comp (ref "R2")
      (value "1k")
      (footprint "eagle-import:R0402")
      (libsource (lib "eagle-import") (part "R0402"))
    )
    (comp (ref "R8")
      (value "1k")
      (footprint "eagle-import:R0402")
      (libsource (lib "eagle-import") (part "R0402"))
    )
    (comp (ref "R11")
      (value "10k")
      (footprint "eagle-import:R0402")
      (libsource (lib "eagle-import") (part "R0402"))
    )
    (comp (ref "R15")
      (value "10k")
      (footprint "eagle-import:R0402")
      (libsource (lib "eagle-import") (part "R0402"))
    )
    (comp (ref "R52")
      (value "10k")
      (footprint "eagle-import:R0402")
      (libsource (lib "eagle-import") (part "R0402"))
    )
    (comp (ref "Y1")
      (value "12Mhz")
      (footprint "eagle-import:MT")
      (libsource (lib "eagle-import") (part "CRYSTAL43.2X2.5"))
    )
    (comp (ref "RV1")
      (value "24V")
      (footprint "eagle-import:R0603")
      (libsource (lib "eagle-import") (part "VARISTOR0603"))
    )
    (comp (ref "RV2")
      (value "24V")
      (footprint "eagle-import:R0603")
      (libsource (lib "eagle-import") (part "VARISTOR0603"))
    )
    (comp (ref "RV3")
      (value "24V")
      (footprint "eagle-import:R0603")
      (libsource (lib "eagle-import") (part "VARISTOR0603"))
    )
    (comp (ref "X1")
      (value "504050-0791")
      (footprint "eagle-import:504050-0791")
      (libsource (lib "eagle-import") (part "504050-0791"))
    )
    (comp (ref "X2")
      (value "504050-0691")
      (footprint "eagle-import:504050-0691")
      (libsource (lib "eagle-import") (part "504050-0691"))
    )
    (comp (ref "X3")
      (value "504050-0491")
      (footprint "eagle-import:504050-0491")
      (libsource (lib "eagle-import") (part "504050-0491"))
    )
    (comp (ref "X4")
      (value "504050-0491")
      (footprint "eagle-import:504050-0491")
      (libsource (lib "eagle-import") (part "504050-0491"))
    )
    (comp (ref "X5")
      (value "504050-1291")
      (footprint "eagle-import:504050-1291")
      (libsource (lib "eagle-import") (part "504050-1291"))
    )
    (comp (ref "X6")
      (value "504050-1291")
      (footprint "eagle-import:504050-1291")
      (libsource (lib "eagle-import") (part "504050-1291"))
    )
  )
  (nets
    (net (code "1") (name "+3V3") (class "Default")
      (node (ref "C22") (pin "1") (pinfunction "1_1") (pintype "passive"))
      (node (ref "C23") (pin "1") (pinfunction "1_1") (pintype "passive"))
      (node (ref "C27") (pin "1") (pinfunction "1_1") (pintype "passive"))
      (node (ref "C5") (pin "1") (pinfunction "1_1") (pintype "passive"))
      (node (ref "C8") (pin "1") (pinfunction "1_1") (pintype "passive"))
      (node (ref "C9") (pin "1") (pinfunction "1_1") (pintype "passive"))
      (node (ref "DBG1") (pin "1") (pinfunction "1_1") (pintype "passive"))
      (node (ref "IC1") (pin "44") (pinfunction "VDD_44") (pintype "bidirectional"))
      (node (ref "IC1") (pin "8") (pinfunction "VDD_8") (pintype "bidirectional"))
      (node (ref "IC2") (pin "30") (pinfunction "VTEMP2_30") (pintype "bidirectional"))
      (node (ref "IC5") (pin "P$10") (pinfunction "EN2_P$10") (pintype "bidirectional"))
      (node (ref "IC5") (pin "P$16") (pinfunction "VDDISO_P$16") (pintype "bidirectional"))
      (node (ref "IC6") (pin "16") (pinfunction "VCC_16") (pintype "bidirectional"))
      (node (ref "IC7") (pin "16") (pinfunction "VCC_16") (pintype "bidirectional"))
      (node (ref "LED1") (pin "A") (pinfunction "A_A") (pintype "passive"))
      (node (ref "LED2") (pin "A") (pinfunction "A_A") (pintype "passive"))
      (node (ref "NTC_R1") (pin "2") (pinfunction "2_2") (pintype "passive"))
      (node (ref "NTC_R10") (pin "2") (pinfunction "2_2") (pintype "passive"))
      (node (ref "NTC_R11") (pin "2") (pinfunction "2_2") (pintype "passive"))
      (node (ref "NTC_R12") (pin "2") (pinfunction "2_2") (pintype "passive"))
      (node (ref "NTC_R2") (pin "2") (pinfunction "2_2") (pintype "passive"))
      (node (ref "NTC_R3") (pin "2") (pinfunction "2_2") (pintype "passive"))
      (node (ref "NTC_R4") (pin "2") (pinfunction "2_2") (pintype "passive"))
      (node (ref "NTC_R5") (pin "2") (pinfunction "2_2") (pintype "passive"))
      (node (ref "NTC_R6") (pin "2") (pinfunction "2_2") (pintype "passive"))
      (node (ref "NTC_R7") (pin "2") (pinfunction "2_2") (pintype "passive"))
      (node (ref "NTC_R8") (pin "2") (pinfunction "2_2") (pintype "passive"))
      (node (ref "NTC_R9") (pin "2") (pinfunction "2_2") (pintype "passive"))
      (node (ref "Q2") (pin "1") (pinfunction "G_1") (pintype "passive"))
      (node (ref "R15") (pin "1") (pinfunction "1_1") (pintype "passive"))
      (node (ref "R19") (pin "2") (pinfunction "2_2") (pintype "passive"))
      (node (ref "R52") (pin "1") (pinfunction "1_1") (pintype "passive"))
      (node (ref "R9") (pin "2") (pinfunction "2_2") (pintype "passive"))
      (node (ref "RGQ1_3") (pin "2") (pinfunction "2_2") (pintype "passive"))
    )
    (net (code "2") (name "BAL1") (class "Default")
      (node (ref "IC2") (pin "25") (pinfunction "S1_25") (pintype "bidirectional"))
      (node (ref "RBG1") (pin "2") (pinfunction "2_2") (pintype "passive"))
    )
    (net (code "3") (name "BAL2") (class "Default")
      (node (ref "IC2") (pin "23") (pinfunction "S2_23") (pintype "bidirectional"))
      (node (ref "RBG2") (pin "2") (pinfunction "2_2") (pintype "passive"))
    )
    (net (code "4") (name "BAL3") (class "Default")
      (node (ref "IC2") (pin "21") (pinfunction "S3_21") (pintype "bidirectional"))
      (node (ref "RBG3") (pin "2") (pinfunction "2_2") (pintype "passive"))
    )
    (net (code "5") (name "BAL4") (class "Default")
      (node (ref "IC2") (pin "19") (pinfunction "S4_19") (pintype "bidirectional"))
      (node (ref "RBG4") (pin "2") (pinfunction "2_2") (pintype "passive"))
    )
    (net (code "6") (name "BAL5") (class "Default")
      (node (ref "IC2") (pin "17") (pinfunction "S5_17") (pintype "bidirectional"))
      (node (ref "RBG5") (pin "2") (pinfunction "2_2") (pintype "passive"))
    )
    (net (code "7") (name "BAL6") (class "Default")
      (node (ref "IC2") (pin "15") (pinfunction "S6_15") (pintype "bidirectional"))
      (node (ref "RBG6") (pin "2") (pinfunction "2_2") (pintype "passive"))
    )
    (net (code "8") (name "BAL7") (class "Default")
      (node (ref "IC2") (pin "13") (pinfunction "S7_13") (pintype "bidirectional"))
      (node (ref "RBG7") (pin "2") (pinfunction "2_2") (pintype "passive"))
    )
    (net (code "9") (name "BAL8") (class "Default")
      (node (ref "IC2") (pin "11") (pinfunction "S8_11") (pintype "bidirectional"))
      (node (ref "RBG8") (pin "2") (pinfunction "2_2") (pintype "passive"))
    )
    (net (code "10") (name "BAL9") (class "Default")
      (node (ref "IC2") (pin "9") (pinfunction "S9_9") (pintype "bidirectional"))
      (node (ref "RBG9") (pin "2") (pinfunction "2_2") (pintype "passive"))
    )
    (net (code "11") (name "BAL10") (class "Default")
      (node (ref "IC2") (pin "7") (pinfunction "S10_7") (pintype "bidirectional"))
      (node (ref "RBG10") (pin "2") (pinfunction "2_2") (pintype "passive"))
    )
    (net (code "12") (name "BAL11") (class "Default")
      (node (ref "IC2") (pin "5") (pinfunction "S11_5") (pintype "bidirectional"))
      (node (ref "RBG11") (pin "2") (pinfunction "2_2") (pintype "passive"))
    )
    (net (code "13") (name "BAL12") (class "Default")
      (node (ref "IC2") (pin "3") (pinfunction "S12_3") (pintype "bidirectional"))
      (node (ref "RBG12") (pin "2") (pinfunction "2_2") (pintype "passive"))
    )
    (net (code "14") (name "C0") (class "Default")
      (node (ref "CCM1") (pin "2") (pinfunction "2_2") (pintype "passive"))
      (node (ref "D1") (pin "A") (pinfunction "A_A") (pintype "passive"))
      (node (ref "DCM1") (pin "A") (pinfunction "A_A") (pintype "passive"))
      (node (ref "IC2") (pin "26") (pinfunction "C0_26") (pintype "bidirectional"))
      (node (ref "RP1") (pin "1") (pinfunction "1_1") (pintype "passive"))
      (node (ref "V-R") (pin "1") (pinfunction "1_1") (pintype "passive"))
      (node (ref "X1") (pin "7") (pinfunction "7_7") (pintype "bidirectional"))
    )
    (net (code "15") (name "C1") (class "Default")
      (node (ref "QB1") (pin "2") (pinfunction "S_2") (pintype "passive"))
      (node (ref "RCM1") (pin "1") (pinfunction "1_1") (pintype "passive"))
      (node (ref "RP2") (pin "1") (pinfunction "1_1") (pintype "passive"))
      (node (ref "X2") (pin "1") (pinfunction "1_1") (pintype "bidirectional"))
    )
    (net (code "16") (name "C1M") (class "Default")
      (node (ref "CCM1") (pin "1") (pinfunction "1_1") (pintype "passive"))
      (node (ref "CCM2") (pin "2") (pinfunction "2_2") (pintype "passive"))
      (node (ref "DCM1") (pin "C") (pinfunction "C_C") (pintype "passive"))
      (node (ref "DCM2") (pin "A") (pinfunction "A_A") (pintype "passive"))
      (node (ref "IC2") (pin "24") (pinfunction "C1_24") (pintype "bidirectional"))
      (node (ref "RCM1") (pin "2") (pinfunction "2_2") (pintype "passive"))
    )
    (net (code "17") (name "C2") (class "Default")
      (node (ref "QB2") (pin "2") (pinfunction "S_2") (pintype "passive"))
      (node (ref "RCM2") (pin "1") (pinfunction "1_1") (pintype "passive"))
      (node (ref "RP3") (pin "1") (pinfunction "1_1") (pintype "passive"))
      (node (ref "X1") (pin "6") (pinfunction "6_6") (pintype "bidirectional"))
    )
    (net (code "18") (name "C2M") (class "Default")
      (node (ref "CCM2") (pin "1") (pinfunction "1_1") (pintype "passive"))
      (node (ref "CCM3") (pin "2") (pinfunction "2_2") (pintype "passive"))
      (node (ref "DCM2") (pin "C") (pinfunction "C_C") (pintype "passive"))
      (node (ref "DCM3") (pin "A") (pinfunction "A_A") (pintype "passive"))
      (node (ref "IC2") (pin "22") (pinfunction "C2_22") (pintype "bidirectional"))
      (node (ref "RCM2") (pin "2") (pinfunction "2_2") (pintype "passive"))
    )
    (net (code "19") (name "C3") (class "Default")
      (node (ref "QB3") (pin "2") (pinfunction "S_2") (pintype "passive"))
      (node (ref "RCM3") (pin "1") (pinfunction "1_1") (pintype "passive"))
      (node (ref "RP4") (pin "1") (pinfunction "1_1") (pintype "passive"))
      (node (ref "X2") (pin "2") (pinfunction "2_2") (pintype "bidirectional"))
    )
    (net (code "20") (name "C3M") (class "Default")
      (node (ref "CCM3") (pin "1") (pinfunction "1_1") (pintype "passive"))
      (node (ref "CCM4") (pin "2") (pinfunction "2_2") (pintype "passive"))
      (node (ref "DCM3") (pin "C") (pinfunction "C_C") (pintype "passive"))
      (node (ref "DCM4") (pin "A") (pinfunction "A_A") (pintype "passive"))
      (node (ref "IC2") (pin "20") (pinfunction "C3_20") (pintype "bidirectional"))
      (node (ref "RCM3") (pin "2") (pinfunction "2_2") (pintype "passive"))
    )
    (net (code "21") (name "C4") (class "Default")
      (node (ref "QB4") (pin "2") (pinfunction "S_2") (pintype "passive"))
      (node (ref "RCM4") (pin "1") (pinfunction "1_1") (pintype "passive"))
      (node (ref "RP5") (pin "1") (pinfunction "1_1") (pintype "passive"))
      (node (ref "X1") (pin "5") (pinfunction "5_5") (pintype "bidirectional"))
    )
    (net (code "22") (name "C4M") (class "Default")
      (node (ref "CCM4") (pin "1") (pinfunction "1_1") (pintype "passive"))
      (node (ref "CCM5") (pin "2") (pinfunction "2_2") (pintype "passive"))
      (node (ref "DCM4") (pin "C") (pinfunction "C_C") (pintype "passive"))
      (node (ref "DCM5") (pin "A") (pinfunction "A_A") (pintype "passive"))
      (node (ref "IC2") (pin "18") (pinfunction "C4_18") (pintype "bidirectional"))
      (node (ref "RCM4") (pin "2") (pinfunction "2_2") (pintype "passive"))
    )
    (net (code "23") (name "C5") (class "Default")
      (node (ref "QB5") (pin "2") (pinfunction "S_2") (pintype "passive"))
      (node (ref "RCM5") (pin "1") (pinfunction "1_1") (pintype "passive"))
      (node (ref "RP6") (pin "1") (pinfunction "1_1") (pintype "passive"))
      (node (ref "X2") (pin "3") (pinfunction "3_3") (pintype "bidirectional"))
    )
    (net (code "24") (name "C5M") (class "Default")
      (node (ref "CCM5") (pin "1") (pinfunction "1_1") (pintype "passive"))
      (node (ref "CCM6") (pin "2") (pinfunction "2_2") (pintype "passive"))
      (node (ref "DCM5") (pin "C") (pinfunction "C_C") (pintype "passive"))
      (node (ref "DCM6") (pin "A") (pinfunction "A_A") (pintype "passive"))
      (node (ref "IC2") (pin "16") (pinfunction "C5_16") (pintype "bidirectional"))
      (node (ref "RCM5") (pin "2") (pinfunction "2_2") (pintype "passive"))
    )
    (net (code "25") (name "C6") (class "Default")
      (node (ref "QB6") (pin "2") (pinfunction "S_2") (pintype "passive"))
      (node (ref "RCM6") (pin "1") (pinfunction "1_1") (pintype "passive"))
      (node (ref "RP7") (pin "1") (pinfunction "1_1") (pintype "passive"))
      (node (ref "X1") (pin "4") (pinfunction "4_4") (pintype "bidirectional"))
    )
    (net (code "26") (name "C6M") (class "Default")
      (node (ref "CCM6") (pin "1") (pinfunction "1_1") (pintype "passive"))
      (node (ref "CCM7") (pin "2") (pinfunction "2_2") (pintype "passive"))
      (node (ref "DCM6") (pin "C") (pinfunction "C_C") (pintype "passive"))
      (node (ref "DCM7") (pin "A") (pinfunction "A_A") (pintype "passive"))
      (node (ref "IC2") (pin "14") (pinfunction "C6_14") (pintype "bidirectional"))
      (node (ref "RCM6") (pin "2") (pinfunction "2_2") (pintype "passive"))
    )
    (net (code "27") (name "C7") (class "Default")
      (node (ref "QB7") (pin "2") (pinfunction "S_2") (pintype "passive"))
      (node (ref "RCM7") (pin "1") (pinfunction "1_1") (pintype "passive"))
      (node (ref "RP8") (pin "1") (pinfunction "1_1") (pintype "passive"))
      (node (ref "X2") (pin "4") (pinfunction "4_4") (pintype "bidirectional"))
    )
    (net (code "28") (name "C7M") (class "Default")
      (node (ref "CCM7") (pin "1") (pinfunction "1_1") (pintype "passive"))
      (node (ref "CCM8") (pin "2") (pinfunction "2_2") (pintype "passive"))
      (node (ref "DCM7") (pin "C") (pinfunction "C_C") (pintype "passive"))
      (node (ref "DCM8") (pin "A") (pinfunction "A_A") (pintype "passive"))
      (node (ref "IC2") (pin "12") (pinfunction "C7_12") (pintype "bidirectional"))
      (node (ref "RCM7") (pin "2") (pinfunction "2_2") (pintype "passive"))
    )
    (net (code "29") (name "C8") (class "Default")
      (node (ref "QB8") (pin "2") (pinfunction "S_2") (pintype "passive"))
      (node (ref "RCM8") (pin "1") (pinfunction "1_1") (pintype "passive"))
      (node (ref "RP9") (pin "1") (pinfunction "1_1") (pintype "passive"))
      (node (ref "X1") (pin "3") (pinfunction "3_3") (pintype "bidirectional"))
    )
    (net (code "30") (name "C8M") (class "Default")
      (node (ref "CCM8") (pin "1") (pinfunction "1_1") (pintype "passive"))
      (node (ref "CCM9") (pin "2") (pinfunction "2_2") (pintype "passive"))
      (node (ref "DCM8") (pin "C") (pinfunction "C_C") (pintype "passive"))
      (node (ref "DCM9") (pin "A") (pinfunction "A_A") (pintype "passive"))
      (node (ref "IC2") (pin "10") (pinfunction "C8_10") (pintype "bidirectional"))
      (node (ref "RCM8") (pin "2") (pinfunction "2_2") (pintype "passive"))
    )
    (net (code "31") (name "C9") (class "Default")
      (node (ref "QB9") (pin "2") (pinfunction "S_2") (pintype "passive"))
      (node (ref "RCM9") (pin "1") (pinfunction "1_1") (pintype "passive"))
      (node (ref "RP10") (pin "1") (pinfunction "1_1") (pintype "passive"))
      (node (ref "X2") (pin "5") (pinfunction "5_5") (pintype "bidirectional"))
    )
    (net (code "32") (name "C9M") (class "Default")
      (node (ref "CCM10") (pin "2") (pinfunction "2_2") (pintype "passive"))
      (node (ref "CCM9") (pin "1") (pinfunction "1_1") (pintype "passive"))
      (node (ref "DCM10") (pin "A") (pinfunction "A_A") (pintype "passive"))
      (node (ref "DCM9") (pin "C") (pinfunction "C_C") (pintype "passive"))
      (node (ref "IC2") (pin "8") (pinfunction "C9_8") (pintype "bidirectional"))
      (node (ref "RCM9") (pin "2") (pinfunction "2_2") (pintype "passive"))
    )
    (net (code "33") (name "C10") (class "Default")
      (node (ref "QB10") (pin "2") (pinfunction "S_2") (pintype "passive"))
      (node (ref "RCM10") (pin "1") (pinfunction "1_1") (pintype "passive"))
      (node (ref "RP11") (pin "1") (pinfunction "1_1") (pintype "passive"))
      (node (ref "X1") (pin "2") (pinfunction "2_2") (pintype "bidirectional"))
    )
    (net (code "34") (name "C10M") (class "Default")
      (node (ref "CCM10") (pin "1") (pinfunction "1_1") (pintype "passive"))
      (node (ref "CCM11") (pin "2") (pinfunction "2_2") (pintype "passive"))
      (node (ref "DCM10") (pin "C") (pinfunction "C_C") (pintype "passive"))
      (node (ref "DCM11") (pin "A") (pinfunction "A_A") (pintype "passive"))
      (node (ref "IC2") (pin "6") (pinfunction "C10_6") (pintype "bidirectional"))
      (node (ref "RCM10") (pin "2") (pinfunction "2_2") (pintype "passive"))
    )
    (net (code "35") (name "C11") (class "Default")
      (node (ref "QB11") (pin "2") (pinfunction "S_2") (pintype "passive"))
      (node (ref "RCM11") (pin "1") (pinfunction "1_1") (pintype "passive"))
      (node (ref "RP12") (pin "1") (pinfunction "1_1") (pintype "passive"))
      (node (ref "X2") (pin "6") (pinfunction "6_6") (pintype "bidirectional"))
    )
    (net (code "36") (name "C11M") (class "Default")
      (node (ref "CCM11") (pin "1") (pinfunction "1_1") (pintype "passive"))
      (node (ref "CCM12") (pin "2") (pinfunction "2_2") (pintype "passive"))
      (node (ref "DCM11") (pin "C") (pinfunction "C_C") (pintype "passive"))
      (node (ref "DCM12") (pin "A") (pinfunction "A_A") (pintype "passive"))
      (node (ref "IC2") (pin "4") (pinfunction "C11_4") (pintype "bidirectional"))
      (node (ref "RCM11") (pin "2") (pinfunction "2_2") (pintype "passive"))
    )
    (net (code "37") (name "C12") (class "Default")
      (node (ref "L7") (pin "1") (pinfunction "1_1") (pintype "passive"))
      (node (ref "QB12") (pin "2") (pinfunction "S_2") (pintype "passive"))
      (node (ref "RCM12") (pin "1") (pinfunction "1_1") (pintype "passive"))
      (node (ref "X1") (pin "1") (pinfunction "1_1") (pintype "bidirectional"))
    )
    (net (code "38") (name "C12M") (class "Default")
      (node (ref "CCM12") (pin "1") (pinfunction "1_1") (pintype "passive"))
      (node (ref "DCM12") (pin "C") (pinfunction "C_C") (pintype "passive"))
      (node (ref "IC2") (pin "2") (pinfunction "C12_2") (pintype "bidirectional"))
      (node (ref "RCM12") (pin "2") (pinfunction "2_2") (pintype "passive"))
    )
    (net (code "39") (name "CANH") (class "Default")
      (node (ref "L12") (pin "4") (pinfunction "4_4") (pintype "passive"))
      (node (ref "RV2") (pin "1") (pinfunction "1_1") (pintype "passive"))
      (node (ref "X3") (pin "2") (pinfunction "2_2") (pintype "bidirectional"))
      (node (ref "X4") (pin "2") (pinfunction "2_2") (pintype "bidirectional"))
    )
    (net (code "40") (name "CANL") (class "Default")
      (node (ref "L12") (pin "3") (pinfunction "2_3") (pintype "passive"))
      (node (ref "RV3") (pin "1") (pinfunction "1_1") (pintype "passive"))
      (node (ref "X3") (pin "3") (pinfunction "3_3") (pintype "bidirectional"))
      (node (ref "X4") (pin "3") (pinfunction "3_3") (pintype "bidirectional"))
    )
    (net (code "41") (name "CANRX") (class "Default")
      (node (ref "IC1") (pin "19") (pinfunction "CANRX_19") (pintype "bidirectional"))
      (node (ref "IC5") (pin "P$14") (pinfunction "O1_P$14") (pintype "bidirectional"))
    )
    (net (code "42") (name "CANTX") (class "Default")
      (node (ref "IC1") (pin "20") (pinfunction "CANTX_20") (pintype "bidirectional"))
      (node (ref "IC5") (pin "P$13") (pinfunction "I2_P$13") (pintype "bidirectional"))
    )
    (net (code "43") (name "CAR+5V") (class "Default")
      (node (ref "C17") (pin "1") (pinfunction "1_1") (pintype "passive"))
      (node (ref "C6") (pin "1") (pinfunction "1_1") (pintype "passive"))
      (node (ref "C7") (pin "1") (pinfunction "1_1") (pintype "passive"))
      (node (ref "IC4") (pin "3") (pinfunction "VDD_3") (pintype "bidirectional"))
      (node (ref "IC5") (pin "P$1") (pinfunction "VDD_P$1") (pintype "bidirectional"))
      (node (ref "IC5") (pin "P$6") (pinfunction "RCSEL_P$6") (pintype "bidirectional"))
      (node (ref "IC5") (pin "P$7") (pinfunction "EN1_P$7") (pintype "bidirectional"))
      (node (ref "IC8") (pin "3") (pinfunction "FB_3") (pintype "bidirectional"))
      (node (ref "REG5_C3") (pin "1") (pinfunction "1_1") (pintype "passive"))
      (node (ref "REG5_L") (pin "2") (pinfunction "2_2") (pintype "passive"))
    )
    (net (code "44") (name "CARGND") (class "Default")
      (node (ref "C17") (pin "2") (pinfunction "2_2") (pintype "passive"))
      (node (ref "C6") (pin "2") (pinfunction "2_2") (pintype "passive"))
      (node (ref "C7") (pin "2") (pinfunction "2_2") (pintype "passive"))
      (node (ref "IC4") (pin "2") (pinfunction "VSS_2") (pintype "bidirectional"))
      (node (ref "IC5") (pin "P$2") (pinfunction "GND_P$2") (pintype "bidirectional"))
      (node (ref "IC5") (pin "P$5") (pinfunction "RCIN_P$5") (pintype "bidirectional"))
      (node (ref "IC5") (pin "P$8") (pinfunction "GND_P$8") (pintype "bidirectional"))
      (node (ref "IC8") (pin "2") (pinfunction "GND_2") (pintype "bidirectional"))
      (node (ref "R39") (pin "2") (pinfunction "2_2") (pintype "passive"))
      (node (ref "REG5_C3") (pin "2") (pinfunction "2_2") (pintype "passive"))
      (node (ref "REG5_C4") (pin "2") (pinfunction "2_2") (pintype "passive"))
      (node (ref "REG5_C6") (pin "2") (pinfunction "2_2") (pintype "passive"))
      (node (ref "REG5_D2") (pin "2") (pinfunction "A_2") (pintype "passive"))
      (node (ref "RV1") (pin "2") (pinfunction "2_2") (pintype "passive"))
      (node (ref "RV2") (pin "2") (pinfunction "2_2") (pintype "passive"))
      (node (ref "RV3") (pin "2") (pinfunction "2_2") (pintype "passive"))
      (node (ref "X3") (pin "4") (pinfunction "4_4") (pintype "bidirectional"))
      (node (ref "X4") (pin "4") (pinfunction "4_4") (pintype "bidirectional"))
    )
    (net (code "45") (name "CARVIN") (class "Default")
      (node (ref "L2") (pin "1") (pinfunction "1_1") (pintype "passive"))
      (node (ref "REG5_C4") (pin "1") (pinfunction "1_1") (pintype "passive"))
      (node (ref "RV1") (pin "1") (pinfunction "1_1") (pintype "passive"))
      (node (ref "X3") (pin "1") (pinfunction "1_1") (pintype "bidirectional"))
      (node (ref "X4") (pin "1") (pinfunction "1_1") (pintype "bidirectional"))
    )
    (net (code "46") (name "FSM") (class "Default")
      (node (ref "C2") (pin "1") (pinfunction "1_1") (pintype "passive"))
      (node (ref "C4") (pin "1") (pinfunction "1_1") (pintype "passive"))
      (node (ref "IC1") (pin "33") (pinfunction "PIO1_0/AD1/CT32B1_CAP0_33") (pintype "bidirectional"))
      (node (ref "IC2") (pin "29") (pinfunction "VTEMP1_29") (pintype "bidirectional"))
      (node (ref "R59") (pin "1") (pinfunction "1_1") (pintype "passive"))
      (node (ref "R60") (pin "2") (pinfunction "2_2") (pintype "passive"))
    )
    (net (code "47") (name "GND") (class "Default")
      (node (ref "C1") (pin "2") (pinfunction "2_2") (pintype "passive"))
      (node (ref "C14") (pin "1") (pinfunction "1_1") (pintype "passive"))
      (node (ref "C15") (pin "1") (pinfunction "1_1") (pintype "passive"))
      (node (ref "C2") (pin "2") (pinfunction "2_2") (pintype "passive"))
      (node (ref "C22") (pin "2") (pinfunction "2_2") (pintype "passive"))
      (node (ref "C23") (pin "2") (pinfunction "2_2") (pintype "passive"))
      (node (ref "C27") (pin "2") (pinfunction "2_2") (pintype "passive"))
      (node (ref "C3") (pin "2") (pinfunction "2_2") (pintype "passive"))
      (node (ref "C34") (pin "2") (pinfunction "2_2") (pintype "passive"))
      (node (ref "C4") (pin "2") (pinfunction "2_2") (pintype "passive"))
      (node (ref "C5") (pin "2") (pinfunction "2_2") (pintype "passive"))
      (node (ref "C8") (pin "2") (pinfunction "2_2") (pintype "passive"))
      (node (ref "C9") (pin "2") (pinfunction "2_2") (pintype "passive"))
      (node (ref "CVREF") (pin "1") (pinfunction "1_1") (pintype "passive"))
      (node (ref "CVREG") (pin "1") (pinfunction "1_1") (pintype "passive"))
      (node (ref "DBG1") (pin "3") (pinfunction "3_3") (pintype "passive"))
      (node (ref "DBG1") (pin "5") (pinfunction "5_5") (pintype "passive"))
      (node (ref "DT1") (pin "C") (pinfunction "C_C") (pintype "passive"))
      (node (ref "DT2") (pin "C") (pinfunction "C_C") (pintype "passive"))
      (node (ref "DT3") (pin "C") (pinfunction "C_C") (pintype "passive"))
      (node (ref "DT4") (pin "C") (pinfunction "C_C") (pintype "passive"))
      (node (ref "DT5") (pin "C") (pinfunction "C_C") (pintype "passive"))
      (node (ref "DT6") (pin "C") (pinfunction "C_C") (pintype "passive"))
      (node (ref "IC1") (pin "41") (pinfunction "VSS_41") (pintype "bidirectional"))
      (node (ref "IC1") (pin "5") (pinfunction "VSS_5") (pintype "bidirectional"))
      (node (ref "IC2") (pin "27") (pinfunction "V-_27") (pintype "bidirectional"))
      (node (ref "IC2") (pin "33") (pinfunction "TOS_33") (pintype "bidirectional"))
      (node (ref "IC2") (pin "34") (pinfunction "WDTB_34") (pintype "bidirectional"))
      (node (ref "IC2") (pin "35") (pinfunction "GPIO1_35") (pintype "bidirectional"))
      (node (ref "IC2") (pin "36") (pinfunction "GPIO2_36") (pintype "bidirectional"))
      (node (ref "IC2") (pin "37") (pinfunction "A0_37") (pintype "bidirectional"))
      (node (ref "IC2") (pin "38") (pinfunction "A1_38") (pintype "bidirectional"))
      (node (ref "IC2") (pin "39") (pinfunction "A2_39") (pintype "bidirectional"))
      (node (ref "IC2") (pin "40") (pinfunction "A3_40") (pintype "bidirectional"))
      (node (ref "IC5") (pin "P$11") (pinfunction "VSEL_P$11") (pintype "bidirectional"))
      (node (ref "IC5") (pin "P$15") (pinfunction "GNDISO_P$15") (pintype "bidirectional"))
      (node (ref "IC5") (pin "P$9") (pinfunction "GNDISO_P$9") (pintype "bidirectional"))
      (node (ref "IC6") (pin "6") (pinfunction "~{E}_6") (pintype "bidirectional"))
      (node (ref "IC6") (pin "7") (pinfunction "VSS_7") (pintype "bidirectional"))
      (node (ref "IC6") (pin "8") (pinfunction "GND_8") (pintype "bidirectional"))
      (node (ref "IC7") (pin "6") (pinfunction "~{E}_6") (pintype "bidirectional"))
      (node (ref "IC7") (pin "7") (pinfunction "VSS_7") (pintype "bidirectional"))
      (node (ref "IC7") (pin "8") (pinfunction "GND_8") (pintype "bidirectional"))
      (node (ref "NTC_C1") (pin "2") (pinfunction "2_2") (pintype "passive"))
      (node (ref "NTC_C10") (pin "2") (pinfunction "2_2") (pintype "passive"))
      (node (ref "NTC_C11") (pin "2") (pinfunction "2_2") (pintype "passive"))
      (node (ref "NTC_C12") (pin "2") (pinfunction "2_2") (pintype "passive"))
      (node (ref "NTC_C2") (pin "2") (pinfunction "2_2") (pintype "passive"))
      (node (ref "NTC_C3") (pin "2") (pinfunction "2_2") (pintype "passive"))
      (node (ref "NTC_C4") (pin "2") (pinfunction "2_2") (pintype "passive"))
      (node (ref "NTC_C5") (pin "2") (pinfunction "2_2") (pintype "passive"))
      (node (ref "NTC_C6") (pin "2") (pinfunction "2_2") (pintype "passive"))
      (node (ref "NTC_C7") (pin "2") (pinfunction "2_2") (pintype "passive"))
      (node (ref "NTC_C8") (pin "2") (pinfunction "2_2") (pintype "passive"))
      (node (ref "NTC_C9") (pin "2") (pinfunction "2_2") (pintype "passive"))
      (node (ref "Q2") (pin "2") (pinfunction "S_2") (pintype "passive"))
      (node (ref "R11") (pin "1") (pinfunction "1_1") (pintype "passive"))
      (node (ref "R60") (pin "1") (pinfunction "1_1") (pintype "passive"))
      (node (ref "RGQ1_3") (pin "1") (pinfunction "1_1") (pintype "passive"))
      (node (ref "V-R") (pin "2") (pinfunction "2_2") (pintype "passive"))
      (node (ref "X2") (pin "P1") (pinfunction "P1_P1") (pintype "bidirectional"))
      (node (ref "X5") (pin "1") (pinfunction "1_1") (pintype "bidirectional"))
      (node (ref "X5") (pin "11") (pinfunction "11_11") (pintype "bidirectional"))
      (node (ref "X5") (pin "3") (pinfunction "3_3") (pintype "bidirectional"))
      (node (ref "X5") (pin "5") (pinfunction "5_5") (pintype "bidirectional"))
      (node (ref "X5") (pin "7") (pinfunction "7_7") (pintype "bidirectional"))
      (node (ref "X5") (pin "9") (pinfunction "9_9") (pintype "bidirectional"))
      (node (ref "X5") (pin "P1") (pinfunction "P1_P1") (pintype "bidirectional"))
      (node (ref "X5") (pin "P2") (pinfunction "P2_P2") (pintype "bidirectional"))
      (node (ref "X6") (pin "1") (pinfunction "1_1") (pintype "bidirectional"))
      (node (ref "X6") (pin "11") (pinfunction "11_11") (pintype "bidirectional"))
      (node (ref "X6") (pin "3") (pinfunction "3_3") (pintype "bidirectional"))
      (node (ref "X6") (pin "5") (pinfunction "5_5") (pintype "bidirectional"))
      (node (ref "X6") (pin "7") (pinfunction "7_7") (pintype "bidirectional"))
      (node (ref "X6") (pin "9") (pinfunction "9_9") (pintype "bidirectional"))
      (node (ref "Y1") (pin "P2") (pinfunction "GND_P2") (pintype "bidirectional"))
      (node (ref "Y1") (pin "P4") (pinfunction "GND1_P4") (pintype "bidirectional"))
    )
    (net (code "48") (name "ISP_CAN") (class "Default")
      (node (ref "IC1") (pin "14") (pinfunction "PIO0_3_14") (pintype "bidirectional"))
      (node (ref "R11") (pin "2") (pinfunction "2_2") (pintype "passive"))
    )
    (net (code "49") (name "ISP_ENTER") (class "Default")
      (node (ref "IC1") (pin "4") (pinfunction "PIO0_1/CLKOUT/CT32B0_MAT2_4") (pintype "bidirectional"))
      (node (ref "R15") (pin "2") (pinfunction "2_2") (pintype "passive"))
    )
    (net (code "50") (name "LED1") (class "Default")
      (node (ref "IC1") (pin "24") (pinfunction "PIO2_9_24") (pintype "bidirectional"))
      (node (ref "R2") (pin "1") (pinfunction "1_1") (pintype "passive"))
    )
    (net (code "51") (name "LED2") (class "Default")
      (node (ref "IC1") (pin "25") (pinfunction "PIO2_10_25") (pintype "bidirectional"))
      (node (ref "R8") (pin "1") (pinfunction "1_1") (pintype "passive"))
    )
    (net (code "52") (name "MISO0") (class "Default")
      (node (ref "IC1") (pin "27") (pinfunction "PIO0_8/MISO0/CT16B0_MAT0_27") (pintype "bidirectional"))
      (node (ref "IC2") (pin "43") (pinfunction "SDO_43") (pintype "bidirectional"))
      (node (ref "R19") (pin "1") (pinfunction "1_1") (pintype "passive"))
    )
    (net (code "53") (name "MISO1") (class "Default")
      (node (ref "IC1") (pin "26") (pinfunction "PIO2_2/~{DCD}/MISO1_26") (pintype "bidirectional"))
    )
    (net (code "54") (name "MOSI0") (class "Default")
      (node (ref "IC1") (pin "28") (pinfunction "PIO0_9/MOSI0/CT16B0_MAT1_28") (pintype "bidirectional"))
      (node (ref "IC2") (pin "42") (pinfunction "SDI_42") (pintype "bidirectional"))
    )
    (net (code "55") (name "MOSI1") (class "Default")
      (node (ref "IC1") (pin "38") (pinfunction "PIO2_3/~{RI}/MOSI1_38") (pintype "bidirectional"))
    )
    (net (code "56") (name "Net-(IC1-XTALIN)") (class "Default")
      (node (ref "C15") (pin "2") (pinfunction "2_2") (pintype "passive"))
      (node (ref "IC1") (pin "6") (pinfunction "XTALIN_6") (pintype "bidirectional"))
      (node (ref "Y1") (pin "P3") (pinfunction "2_P3") (pintype "passive"))
    )
    (net (code "57") (name "Net-(IC1-XTALOUT)") (class "Default")
      (node (ref "C14") (pin "2") (pinfunction "2_2") (pintype "passive"))
      (node (ref "IC1") (pin "7") (pinfunction "XTALOUT_7") (pintype "bidirectional"))
      (node (ref "Y1") (pin "P1") (pinfunction "1_P1") (pintype "passive"))
    )
    (net (code "58") (name "Net-(IC4-CANH)") (class "Default")
      (node (ref "IC4") (pin "7") (pinfunction "CANH_7") (pintype "bidirectional"))
      (node (ref "L12") (pin "1") (pinfunction "3_1") (pintype "passive"))
    )
    (net (code "59") (name "Net-(IC4-CANL)") (class "Default")
      (node (ref "IC4") (pin "6") (pinfunction "CANL_6") (pintype "bidirectional"))
      (node (ref "L12") (pin "2") (pinfunction "1_2") (pintype "passive"))
    )
    (net (code "60") (name "Net-(IC4-RS)") (class "Default")
      (node (ref "IC4") (pin "8") (pinfunction "RS_8") (pintype "bidirectional"))
      (node (ref "R39") (pin "1") (pinfunction "1_1") (pintype "passive"))
    )
    (net (code "61") (name "Net-(IC4-RX)") (class "Default")
      (node (ref "IC4") (pin "4") (pinfunction "RX_4") (pintype "bidirectional"))
      (node (ref "R41") (pin "1") (pinfunction "1_1") (pintype "passive"))
    )
    (net (code "62") (name "Net-(IC4-TX)") (class "Default")
      (node (ref "IC4") (pin "1") (pinfunction "TX_1") (pintype "bidirectional"))
      (node (ref "R40") (pin "1") (pinfunction "1_1") (pintype "passive"))
    )
    (net (code "63") (name "Net-(IC5-I1)") (class "Default")
      (node (ref "IC5") (pin "P$3") (pinfunction "I1_P$3") (pintype "bidirectional"))
      (node (ref "R41") (pin "2") (pinfunction "2_2") (pintype "passive"))
    )
    (net (code "64") (name "Net-(IC5-O2)") (class "Default")
      (node (ref "IC5") (pin "P$4") (pinfunction "O2_P$4") (pintype "bidirectional"))
      (node (ref "R40") (pin "2") (pinfunction "2_2") (pintype "passive"))
    )
    (net (code "65") (name "Net-(IC8-CB)") (class "Default")
      (node (ref "IC8") (pin "1") (pinfunction "CB_1") (pintype "bidirectional"))
      (node (ref "REG5_C2") (pin "1") (pinfunction "1_1") (pintype "passive"))
    )
    (net (code "66") (name "Net-(IC8-SW)") (class "Default")
      (node (ref "IC8") (pin "6") (pinfunction "SW_6") (pintype "bidirectional"))
      (node (ref "REG5_C2") (pin "2") (pinfunction "2_2") (pintype "passive"))
      (node (ref "REG5_D2") (pin "1") (pinfunction "C_1") (pintype "passive"))
      (node (ref "REG5_L") (pin "1") (pinfunction "1_1") (pintype "passive"))
    )
    (net (code "67") (name "Net-(IC8-VIN)") (class "Default")
      (node (ref "IC8") (pin "4") (pinfunction "~{SHDN}_4") (pintype "bidirectional"))
      (node (ref "IC8") (pin "5") (pinfunction "VIN_5") (pintype "bidirectional"))
      (node (ref "L2") (pin "2") (pinfunction "2_2") (pintype "passive"))
      (node (ref "REG5_C6") (pin "1") (pinfunction "1_1") (pintype "passive"))
    )
    (net (code "68") (name "Net-(L7-Pad2)") (class "Default")
      (node (ref "L7") (pin "2") (pinfunction "2_2") (pintype "passive"))
      (node (ref "V+R") (pin "1") (pinfunction "1_1") (pintype "passive"))
    )
    (net (code "69") (name "Net-(LED1-PadC)") (class "Default")
      (node (ref "LED1") (pin "C") (pinfunction "C_C") (pintype "passive"))
      (node (ref "R2") (pin "2") (pinfunction "2_2") (pintype "passive"))
    )
    (net (code "70") (name "Net-(LED2-PadC)") (class "Default")
      (node (ref "LED2") (pin "C") (pinfunction "C_C") (pintype "passive"))
      (node (ref "R8") (pin "2") (pinfunction "2_2") (pintype "passive"))
    )
    (net (code "71") (name "Net-(Q1-G)") (class "Default")
      (node (ref "D2") (pin "A") (pinfunction "A_A") (pintype "passive"))
      (node (ref "Q1") (pin "1") (pinfunction "G_1") (pintype "passive"))
      (node (ref "RGQ1_1") (pin "2") (pinfunction "2_2") (pintype "passive"))
      (node (ref "RGQ1_2") (pin "2") (pinfunction "2_2") (pintype "passive"))
    )
    (net (code "72") (name "Net-(Q1-S)") (class "Default")
      (node (ref "D1") (pin "C") (pinfunction "C_C") (pintype "passive"))
      (node (ref "D2") (pin "C") (pinfunction "C_C") (pintype "passive"))
      (node (ref "Q1") (pin "2") (pinfunction "S_2") (pintype "passive"))
      (node (ref "RGQ1_1") (pin "1") (pinfunction "1_1") (pintype "passive"))
      (node (ref "V+R") (pin "2") (pinfunction "2_2") (pintype "passive"))
    )
    (net (code "73") (name "Net-(Q2-D)") (class "Default")
      (node (ref "Q2") (pin "3") (pinfunction "D_3") (pintype "passive"))
      (node (ref "RGQ1_2") (pin "1") (pinfunction "1_1") (pintype "passive"))
    )
    (net (code "74") (name "Net-(QB1-D)") (class "Default")
      (node (ref "QB1") (pin "3") (pinfunction "D_3") (pintype "passive"))
      (node (ref "RP1") (pin "2") (pinfunction "2_2") (pintype "passive"))
    )
    (net (code "75") (name "Net-(QB1-G)") (class "Default")
      (node (ref "QB1") (pin "1") (pinfunction "G_1") (pintype "passive"))
      (node (ref "RBG1") (pin "1") (pinfunction "1_1") (pintype "passive"))
    )
    (net (code "76") (name "Net-(QB2-D)") (class "Default")
      (node (ref "QB2") (pin "3") (pinfunction "D_3") (pintype "passive"))
      (node (ref "RP2") (pin "2") (pinfunction "2_2") (pintype "passive"))
    )
    (net (code "77") (name "Net-(QB2-G)") (class "Default")
      (node (ref "QB2") (pin "1") (pinfunction "G_1") (pintype "passive"))
      (node (ref "RBG2") (pin "1") (pinfunction "1_1") (pintype "passive"))
    )
    (net (code "78") (name "Net-(QB3-D)") (class "Default")
      (node (ref "QB3") (pin "3") (pinfunction "D_3") (pintype "passive"))
      (node (ref "RP3") (pin "2") (pinfunction "2_2") (pintype "passive"))
    )
    (net (code "79") (name "Net-(QB3-G)") (class "Default")
      (node (ref "QB3") (pin "1") (pinfunction "G_1") (pintype "passive"))
      (node (ref "RBG3") (pin "1") (pinfunction "1_1") (pintype "passive"))
    )
    (net (code "80") (name "Net-(QB4-D)") (class "Default")
      (node (ref "QB4") (pin "3") (pinfunction "D_3") (pintype "passive"))
      (node (ref "RP4") (pin "2") (pinfunction "2_2") (pintype "passive"))
    )
    (net (code "81") (name "Net-(QB4-G)") (class "Default")
      (node (ref "QB4") (pin "1") (pinfunction "G_1") (pintype "passive"))
      (node (ref "RBG4") (pin "1") (pinfunction "1_1") (pintype "passive"))
    )
    (net (code "82") (name "Net-(QB5-D)") (class "Default")
      (node (ref "QB5") (pin "3") (pinfunction "D_3") (pintype "passive"))
      (node (ref "RP5") (pin "2") (pinfunction "2_2") (pintype "passive"))
    )
    (net (code "83") (name "Net-(QB5-G)") (class "Default")
      (node (ref "QB5") (pin "1") (pinfunction "G_1") (pintype "passive"))
      (node (ref "RBG5") (pin "1") (pinfunction "1_1") (pintype "passive"))
    )
    (net (code "84") (name "Net-(QB6-D)") (class "Default")
      (node (ref "QB6") (pin "3") (pinfunction "D_3") (pintype "passive"))
      (node (ref "RP6") (pin "2") (pinfunction "2_2") (pintype "passive"))
    )
    (net (code "85") (name "Net-(QB6-G)") (class "Default")
      (node (ref "QB6") (pin "1") (pinfunction "G_1") (pintype "passive"))
      (node (ref "RBG6") (pin "1") (pinfunction "1_1") (pintype "passive"))
    )
    (net (code "86") (name "Net-(QB7-D)") (class "Default")
      (node (ref "QB7") (pin "3") (pinfunction "D_3") (pintype "passive"))
      (node (ref "RP7") (pin "2") (pinfunction "2_2") (pintype "passive"))
    )
    (net (code "87") (name "Net-(QB7-G)") (class "Default")
      (node (ref "QB7") (pin "1") (pinfunction "G_1") (pintype "passive"))
      (node (ref "RBG7") (pin "1") (pinfunction "1_1") (pintype "passive"))
    )
    (net (code "88") (name "Net-(QB8-D)") (class "Default")
      (node (ref "QB8") (pin "3") (pinfunction "D_3") (pintype "passive"))
      (node (ref "RP8") (pin "2") (pinfunction "2_2") (pintype "passive"))
    )
    (net (code "89") (name "Net-(QB8-G)") (class "Default")
      (node (ref "QB8") (pin "1") (pinfunction "G_1") (pintype "passive"))
      (node (ref "RBG8") (pin "1") (pinfunction "1_1") (pintype "passive"))
    )
    (net (code "90") (name "Net-(QB9-D)") (class "Default")
      (node (ref "QB9") (pin "3") (pinfunction "D_3") (pintype "passive"))
      (node (ref "RP9") (pin "2") (pinfunction "2_2") (pintype "passive"))
    )
    (net (code "91") (name "Net-(QB9-G)") (class "Default")
      (node (ref "QB9") (pin "1") (pinfunction "G_1") (pintype "passive"))
      (node (ref "RBG9") (pin "1") (pinfunction "1_1") (pintype "passive"))
    )
    (net (code "92") (name "Net-(QB10-D)") (class "Default")
      (node (ref "QB10") (pin "3") (pinfunction "D_3") (pintype "passive"))
      (node (ref "RP10") (pin "2") (pinfunction "2_2") (pintype "passive"))
    )
    (net (code "93") (name "Net-(QB10-G)") (class "Default")
      (node (ref "QB10") (pin "1") (pinfunction "G_1") (pintype "passive"))
      (node (ref "RBG10") (pin "1") (pinfunction "1_1") (pintype "passive"))
    )
    (net (code "94") (name "Net-(QB11-D)") (class "Default")
      (node (ref "QB11") (pin "3") (pinfunction "D_3") (pintype "passive"))
      (node (ref "RP11") (pin "2") (pinfunction "2_2") (pintype "passive"))
    )
    (net (code "95") (name "Net-(QB11-G)") (class "Default")
      (node (ref "QB11") (pin "1") (pinfunction "G_1") (pintype "passive"))
      (node (ref "RBG11") (pin "1") (pinfunction "1_1") (pintype "passive"))
    )
    (net (code "96") (name "Net-(QB12-D)") (class "Default")
      (node (ref "QB12") (pin "3") (pinfunction "D_3") (pintype "passive"))
      (node (ref "RP12") (pin "2") (pinfunction "2_2") (pintype "passive"))
    )
    (net (code "97") (name "Net-(QB12-G)") (class "Default")
      (node (ref "QB12") (pin "1") (pinfunction "G_1") (pintype "passive"))
      (node (ref "RBG12") (pin "1") (pinfunction "1_1") (pintype "passive"))
    )
    (net (code "98") (name "RXD") (class "Default")
      (node (ref "IC1") (pin "46") (pinfunction "PIO1_6/RXD/CT32B0_MAT0_46") (pintype "bidirectional"))
    )
    (net (code "99") (name "SCK0") (class "Default")
      (node (ref "IC1") (pin "22") (pinfunction "PIO0_6/SCK0_22") (pintype "bidirectional"))
      (node (ref "IC2") (pin "41") (pinfunction "SCKI_41") (pintype "bidirectional"))
    )
    (net (code "100") (name "SCK1") (class "Default")
      (node (ref "IC1") (pin "13") (pinfunction "PIO2_1/~{DSR}/SCK1_13") (pintype "bidirectional"))
    )
    (net (code "101") (name "SSEL0") (class "Default")
      (node (ref "IC1") (pin "10") (pinfunction "PIO0_2/SSEL/CT16B0_CAP0_10") (pintype "bidirectional"))
      (node (ref "IC2") (pin "44") (pinfunction "CSBI_44") (pintype "bidirectional"))
    )
    (net (code "102") (name "SSEL1") (class "Default")
      (node (ref "IC1") (pin "2") (pinfunction "PIO2_0/~{DTR}/SSEL1_2") (pintype "bidirectional"))
    )
    (net (code "103") (name "SWCLK") (class "Default")
      (node (ref "DBG1") (pin "4") (pinfunction "4_4") (pintype "passive"))
      (node (ref "IC1") (pin "29") (pinfunction "PIO0_10/SWCLK/SCK0/CT16B0_MAT2_29") (pintype "bidirectional"))
    )
    (net (code "104") (name "SWDIO") (class "Default")
      (node (ref "DBG1") (pin "2") (pinfunction "2_2") (pintype "passive"))
      (node (ref "IC1") (pin "39") (pinfunction "PIO1_3/SWDIO/AD4/CT32B1_MAT2_39") (pintype "bidirectional"))
    )
    (net (code "105") (name "TEMP0") (class "Default")
      (node (ref "IC6") (pin "1") (pinfunction "A1_1") (pintype "bidirectional"))
      (node (ref "NTC_C3") (pin "1") (pinfunction "1_1") (pintype "passive"))
      (node (ref "NTC_R3") (pin "1") (pinfunction "1_1") (pintype "passive"))
      (node (ref "X5") (pin "2") (pinfunction "2_2") (pintype "bidirectional"))
    )
    (net (code "106") (name "TEMP1") (class "Default")
      (node (ref "IC6") (pin "5") (pinfunction "A2_5") (pintype "bidirectional"))
      (node (ref "NTC_C2") (pin "1") (pinfunction "1_1") (pintype "passive"))
      (node (ref "NTC_R2") (pin "1") (pinfunction "1_1") (pintype "passive"))
      (node (ref "X5") (pin "4") (pinfunction "4_4") (pintype "bidirectional"))
    )
    (net (code "107") (name "TEMP2") (class "Default")
      (node (ref "IC6") (pin "2") (pinfunction "A3_2") (pintype "bidirectional"))
      (node (ref "NTC_C4") (pin "1") (pinfunction "1_1") (pintype "passive"))
      (node (ref "NTC_R4") (pin "1") (pinfunction "1_1") (pintype "passive"))
      (node (ref "X5") (pin "6") (pinfunction "6_6") (pintype "bidirectional"))
    )
    (net (code "108") (name "TEMP3") (class "Default")
      (node (ref "IC6") (pin "12") (pinfunction "B1_12") (pintype "bidirectional"))
      (node (ref "NTC_C1") (pin "1") (pinfunction "1_1") (pintype "passive"))
      (node (ref "NTC_R1") (pin "1") (pinfunction "1_1") (pintype "passive"))
      (node (ref "X5") (pin "8") (pinfunction "8_8") (pintype "bidirectional"))
    )
    (net (code "109") (name "TEMP4") (class "Default")
      (node (ref "IC6") (pin "14") (pinfunction "B2_14") (pintype "bidirectional"))
      (node (ref "NTC_C5") (pin "1") (pinfunction "1_1") (pintype "passive"))
      (node (ref "NTC_R5") (pin "1") (pinfunction "1_1") (pintype "passive"))
      (node (ref "X5") (pin "10") (pinfunction "10_10") (pintype "bidirectional"))
    )
    (net (code "110") (name "TEMP5") (class "Default")
      (node (ref "IC6") (pin "15") (pinfunction "B3_15") (pintype "bidirectional"))
      (node (ref "NTC_C8") (pin "1") (pinfunction "1_1") (pintype "passive"))
      (node (ref "NTC_R8") (pin "1") (pinfunction "1_1") (pintype "passive"))
      (node (ref "X5") (pin "12") (pinfunction "12_12") (pintype "bidirectional"))
    )
    (net (code "111") (name "TEMP6") (class "Default")
      (node (ref "IC7") (pin "1") (pinfunction "A1_1") (pintype "bidirectional"))
      (node (ref "NTC_C6") (pin "1") (pinfunction "1_1") (pintype "passive"))
      (node (ref "NTC_R6") (pin "1") (pinfunction "1_1") (pintype "passive"))
      (node (ref "X6") (pin "2") (pinfunction "2_2") (pintype "bidirectional"))
    )
    (net (code "112") (name "TEMP7") (class "Default")
      (node (ref "IC7") (pin "5") (pinfunction "A2_5") (pintype "bidirectional"))
      (node (ref "NTC_C7") (pin "1") (pinfunction "1_1") (pintype "passive"))
      (node (ref "NTC_R7") (pin "1") (pinfunction "1_1") (pintype "passive"))
      (node (ref "X6") (pin "4") (pinfunction "4_4") (pintype "bidirectional"))
    )
    (net (code "113") (name "TEMP8") (class "Default")
      (node (ref "IC7") (pin "2") (pinfunction "A3_2") (pintype "bidirectional"))
      (node (ref "NTC_C9") (pin "1") (pinfunction "1_1") (pintype "passive"))
      (node (ref "NTC_R9") (pin "1") (pinfunction "1_1") (pintype "passive"))
      (node (ref "X6") (pin "6") (pinfunction "6_6") (pintype "bidirectional"))
    )
    (net (code "114") (name "TEMP9") (class "Default")
      (node (ref "IC7") (pin "12") (pinfunction "B1_12") (pintype "bidirectional"))
      (node (ref "NTC_C12") (pin "1") (pinfunction "1_1") (pintype "passive"))
      (node (ref "NTC_R12") (pin "1") (pinfunction "1_1") (pintype "passive"))
      (node (ref "X6") (pin "8") (pinfunction "8_8") (pintype "bidirectional"))
    )
    (net (code "115") (name "TEMP10") (class "Default")
      (node (ref "IC7") (pin "14") (pinfunction "B2_14") (pintype "bidirectional"))
      (node (ref "NTC_C10") (pin "1") (pinfunction "1_1") (pintype "passive"))
      (node (ref "NTC_R10") (pin "1") (pinfunction "1_1") (pintype "passive"))
      (node (ref "X6") (pin "10") (pinfunction "10_10") (pintype "bidirectional"))
    )
    (net (code "116") (name "TEMP11") (class "Default")
      (node (ref "IC7") (pin "15") (pinfunction "B3_15") (pintype "bidirectional"))
      (node (ref "NTC_C11") (pin "1") (pinfunction "1_1") (pintype "passive"))
      (node (ref "NTC_R11") (pin "1") (pinfunction "1_1") (pintype "passive"))
      (node (ref "X6") (pin "12") (pinfunction "12_12") (pintype "bidirectional"))
    )
    (net (code "117") (name "TEMPR") (class "Default")
      (node (ref "C3") (pin "1") (pinfunction "1_1") (pintype "passive"))
      (node (ref "DT1") (pin "A") (pinfunction "A_A") (pintype "passive"))
      (node (ref "DT2") (pin "A") (pinfunction "A_A") (pintype "passive"))
      (node (ref "DT3") (pin "A") (pinfunction "A_A") (pintype "passive"))
      (node (ref "DT4") (pin "A") (pinfunction "A_A") (pintype "passive"))
      (node (ref "DT5") (pin "A") (pinfunction "A_A") (pintype "passive"))
      (node (ref "DT6") (pin "A") (pinfunction "A_A") (pintype "passive"))
      (node (ref "IC1") (pin "34") (pinfunction "PIO1_1/AD2/CT32B1_MAT0_34") (pintype "bidirectional"))
      (node (ref "R9") (pin "1") (pinfunction "1_1") (pintype "passive"))
    )
    (net (code "118") (name "TS0") (class "Default")
      (node (ref "IC1") (pin "18") (pinfunction "PIO2_4_18") (pintype "bidirectional"))
      (node (ref "IC6") (pin "10") (pinfunction "S0_10") (pintype "bidirectional"))
      (node (ref "IC7") (pin "10") (pinfunction "S0_10") (pintype "bidirectional"))
    )
    (net (code "119") (name "TS1") (class "Default")
      (node (ref "IC1") (pin "21") (pinfunction "PIO2_5_21") (pintype "bidirectional"))
      (node (ref "IC6") (pin "9") (pinfunction "S1_9") (pintype "bidirectional"))
      (node (ref "IC7") (pin "9") (pinfunction "S1_9") (pintype "bidirectional"))
    )
    (net (code "120") (name "TXD") (class "Default")
      (node (ref "IC1") (pin "47") (pinfunction "PIO1_7/TXD/CT32B0_MAT1_47") (pintype "bidirectional"))
    )
    (net (code "121") (name "UCT1") (class "Default")
      (node (ref "IC1") (pin "30") (pinfunction "PIO1_10/AD6/CT16B1_MAT1_30") (pintype "bidirectional"))
      (node (ref "IC6") (pin "3") (pinfunction "A_3") (pintype "bidirectional"))
    )
    (net (code "122") (name "UCT2") (class "Default")
      (node (ref "IC1") (pin "32") (pinfunction "PIO0_11/AD0/CT32B0_MAT3_32") (pintype "bidirectional"))
      (node (ref "IC6") (pin "13") (pinfunction "B_13") (pintype "bidirectional"))
    )
    (net (code "123") (name "UCT3") (class "Default")
      (node (ref "IC1") (pin "35") (pinfunction "PIO1_2/AD3/CT32B1_MAT1_35") (pintype "bidirectional"))
      (node (ref "IC7") (pin "3") (pinfunction "A_3") (pintype "bidirectional"))
    )
    (net (code "124") (name "UCT4") (class "Default")
      (node (ref "IC1") (pin "40") (pinfunction "PIO1_4/AD5/CT32B1_MAT3_40") (pintype "bidirectional"))
      (node (ref "IC7") (pin "13") (pinfunction "B_13") (pintype "bidirectional"))
    )
    (net (code "125") (name "V+") (class "Default")
      (node (ref "C1") (pin "1") (pinfunction "1_1") (pintype "passive"))
      (node (ref "IC2") (pin "1") (pinfunction "V+_1") (pintype "bidirectional"))
      (node (ref "Q1") (pin "3") (pinfunction "D_3") (pintype "passive"))
      (node (ref "R59") (pin "2") (pinfunction "2_2") (pintype "passive"))
    )
    (net (code "126") (name "VREF") (class "Default")
      (node (ref "CVREF") (pin "2") (pinfunction "2_2") (pintype "passive"))
      (node (ref "IC2") (pin "31") (pinfunction "VREF_31") (pintype "bidirectional"))
    )
    (net (code "127") (name "VREG") (class "Default")
      (node (ref "CVREG") (pin "2") (pinfunction "2_2") (pintype "passive"))
      (node (ref "IC2") (pin "32") (pinfunction "VREG_32") (pintype "bidirectional"))
    )
    (net (code "128") (name "WEF1") (class "Default")
      (node (ref "IC1") (pin "42") (pinfunction "PIO1_11/AD7_42") (pintype "bidirectional"))
    )
    (net (code "129") (name "unconnected-(DBG1-Pad6)") (class "Default")
      (node (ref "DBG1") (pin "6") (pinfunction "6_6") (pintype "passive"))
    )
    (net (code "130") (name "unconnected-(DBG1-Pad7)") (class "Default")
      (node (ref "DBG1") (pin "7") (pinfunction "7_7") (pintype "passive"))
    )
    (net (code "131") (name "unconnected-(DBG1-Pad8)") (class "Default")
      (node (ref "DBG1") (pin "8") (pinfunction "8_8") (pintype "passive"))
    )
    (net (code "132") (name "unconnected-(DBG1-Pad9)") (class "Default")
      (node (ref "DBG1") (pin "9") (pinfunction "9_9") (pintype "passive"))
    )
    (net (code "133") (name "unconnected-(IC1-PIO0_4{slash}SCL-Pad15)") (class "Default")
      (node (ref "IC1") (pin "15") (pinfunction "PIO0_4/SCL_15") (pintype "bidirectional"))
    )
    (net (code "134") (name "unconnected-(IC1-PIO0_5{slash}SDA-Pad16)") (class "Default")
      (node (ref "IC1") (pin "16") (pinfunction "PIO0_5/SDA_16") (pintype "bidirectional"))
    )
    (net (code "135") (name "unconnected-(IC1-PIO0_7{slash}~{CTS}-Pad23)") (class "Default")
      (node (ref "IC1") (pin "23") (pinfunction "PIO0_7/~{CTS}_23") (pintype "bidirectional"))
    )
    (net (code "136") (name "unconnected-(IC1-PIO1_5{slash}~{RTS}{slash}CT32B0_CAP0-Pad45)") (class "Default")
      (node (ref "IC1") (pin "45") (pinfunction "PIO1_5/~{RTS}/CT32B0_CAP0_45") (pintype "bidirectional"))
    )
    (net (code "137") (name "unconnected-(IC1-PIO1_8{slash}CT16B1_CAP0-Pad9)") (class "Default")
      (node (ref "IC1") (pin "9") (pinfunction "PIO1_8/CT16B1_CAP0_9") (pintype "bidirectional"))
    )
    (net (code "138") (name "unconnected-(IC1-PIO1_9{slash}CT16B1_MAT0-Pad17)") (class "Default")
      (node (ref "IC1") (pin "17") (pinfunction "PIO1_9/CT16B1_MAT0_17") (pintype "bidirectional"))
    )
    (net (code "139") (name "unconnected-(IC1-PIO2_6-Pad1)") (class "Default")
      (node (ref "IC1") (pin "1") (pinfunction "PIO2_6_1") (pintype "bidirectional"))
    )
    (net (code "140") (name "unconnected-(IC1-PIO2_7-Pad11)") (class "Default")
      (node (ref "IC1") (pin "11") (pinfunction "PIO2_7_11") (pintype "bidirectional"))
    )
    (net (code "141") (name "unconnected-(IC1-PIO2_8-Pad12)") (class "Default")
      (node (ref "IC1") (pin "12") (pinfunction "PIO2_8_12") (pintype "bidirectional"))
    )
    (net (code "142") (name "unconnected-(IC1-PIO2_11{slash}SCK0-Pad31)") (class "Default")
      (node (ref "IC1") (pin "31") (pinfunction "PIO2_11/SCK0_31") (pintype "bidirectional"))
    )
    (net (code "143") (name "unconnected-(IC1-PIO3_0{slash}~{DTR}-Pad36)") (class "Default")
      (node (ref "IC1") (pin "36") (pinfunction "PIO3_0/~{DTR}_36") (pintype "bidirectional"))
    )
    (net (code "144") (name "unconnected-(IC1-PIO3_1{slash}~{DSR}-Pad37)") (class "Default")
      (node (ref "IC1") (pin "37") (pinfunction "PIO3_1/~{DSR}_37") (pintype "bidirectional"))
    )
    (net (code "145") (name "unconnected-(IC1-PIO3_2{slash}~{DCD}-Pad43)") (class "Default")
      (node (ref "IC1") (pin "43") (pinfunction "PIO3_2/~{DCD}_43") (pintype "bidirectional"))
    )
    (net (code "146") (name "unconnected-(IC1-PIO3_3{slash}~{RI}-Pad48)") (class "Default")
      (node (ref "IC1") (pin "48") (pinfunction "PIO3_3/~{RI}_48") (pintype "bidirectional"))
    )
    (net (code "147") (name "unconnected-(IC4-VRF-Pad5)") (class "Default")
      (node (ref "IC4") (pin "5") (pinfunction "VRF_5") (pintype "bidirectional"))
    )
    (net (code "148") (name "unconnected-(IC6-A4-Pad4)") (class "Default")
      (node (ref "IC6") (pin "4") (pinfunction "A4_4") (pintype "bidirectional"))
    )
    (net (code "149") (name "unconnected-(IC6-B4-Pad11)") (class "Default")
      (node (ref "IC6") (pin "11") (pinfunction "B4_11") (pintype "bidirectional"))
    )
    (net (code "150") (name "unconnected-(IC7-A4-Pad4)") (class "Default")
      (node (ref "IC7") (pin "4") (pinfunction "A4_4") (pintype "bidirectional"))
    )
    (net (code "151") (name "unconnected-(IC7-B4-Pad11)") (class "Default")
      (node (ref "IC7") (pin "11") (pinfunction "B4_11") (pintype "bidirectional"))
    )
    (net (code "152") (name "unconnected-(X1-PadP1)") (class "Default")
      (node (ref "X1") (pin "P1") (pinfunction "P1_P1") (pintype "bidirectional"))
    )
    (net (code "153") (name "unconnected-(X1-PadP2)") (class "Default")
      (node (ref "X1") (pin "P2") (pinfunction "P2_P2") (pintype "bidirectional"))
    )
    (net (code "154") (name "unconnected-(X2-PadP2)") (class "Default")
      (node (ref "X2") (pin "P2") (pinfunction "P2_P2") (pintype "bidirectional"))
    )
    (net (code "155") (name "unconnected-(X3-PadP1)") (class "Default")
      (node (ref "X3") (pin "P1") (pinfunction "P1_P1") (pintype "bidirectional"))
    )
    (net (code "156") (name "unconnected-(X3-PadP2)") (class "Default")
      (node (ref "X3") (pin "P2") (pinfunction "P2_P2") (pintype "bidirectional"))
    )
    (net (code "157") (name "unconnected-(X4-PadP1)") (class "Default")
      (node (ref "X4") (pin "P1") (pinfunction "P1_P1") (pintype "bidirectional"))
    )
    (net (code "158") (name "unconnected-(X4-PadP2)") (class "Default")
      (node (ref "X4") (pin "P2") (pinfunction "P2_P2") (pintype "bidirectional"))
    )
    (net (code "159") (name "unconnected-(X6-PadP1)") (class "Default")
      (node (ref "X6") (pin "P1") (pinfunction "P1_P1") (pintype "bidirectional"))
    )
    (net (code "160") (name "unconnected-(X6-PadP2)") (class "Default")
      (node (ref "X6") (pin "P2") (pinfunction "P2_P2") (pintype "bidirectional"))
    )
    (net (code "161") (name "~{RESET}") (class "Default")
      (node (ref "C34") (pin "1") (pinfunction "1_1") (pintype "passive"))
      (node (ref "DBG1") (pin "10") (pinfunction "10_10") (pintype "passive"))
      (node (ref "IC1") (pin "3") (pinfunction "PIO0_0/~{RESET}_3") (pintype "bidirectional"))
      (node (ref "R52") (pin "2") (pinfunction "2_2") (pintype "passive"))
    )
  )
)
